# WM1302_v1_1_868_SPI.net
KiCad netlist of a schematic drawn in EAGLE
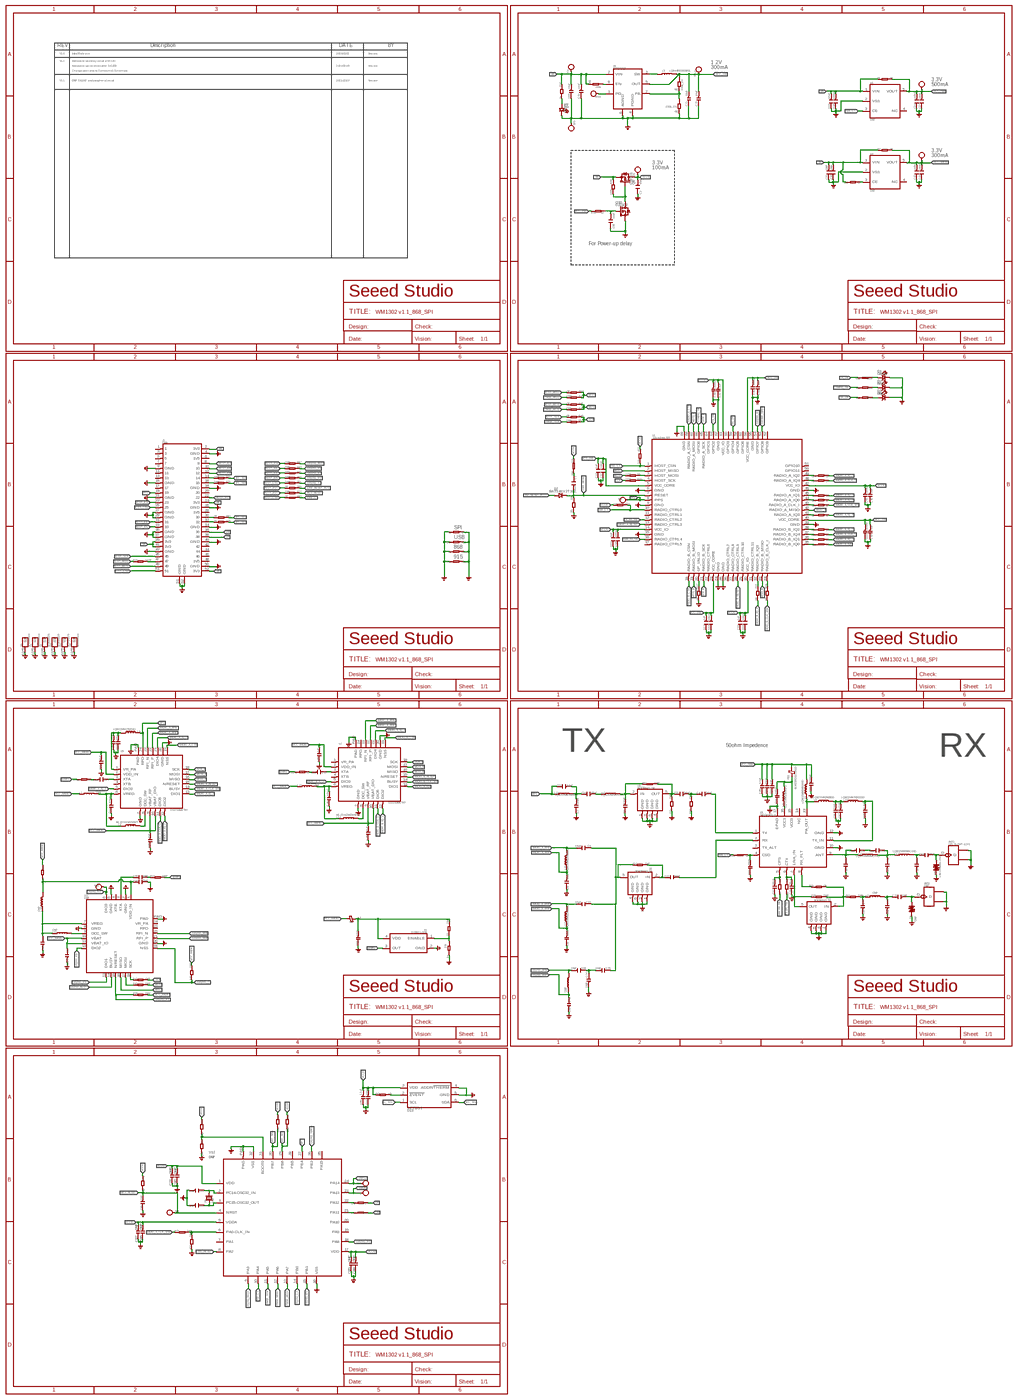
[diagram p0: schematic, sheet 1, overview]
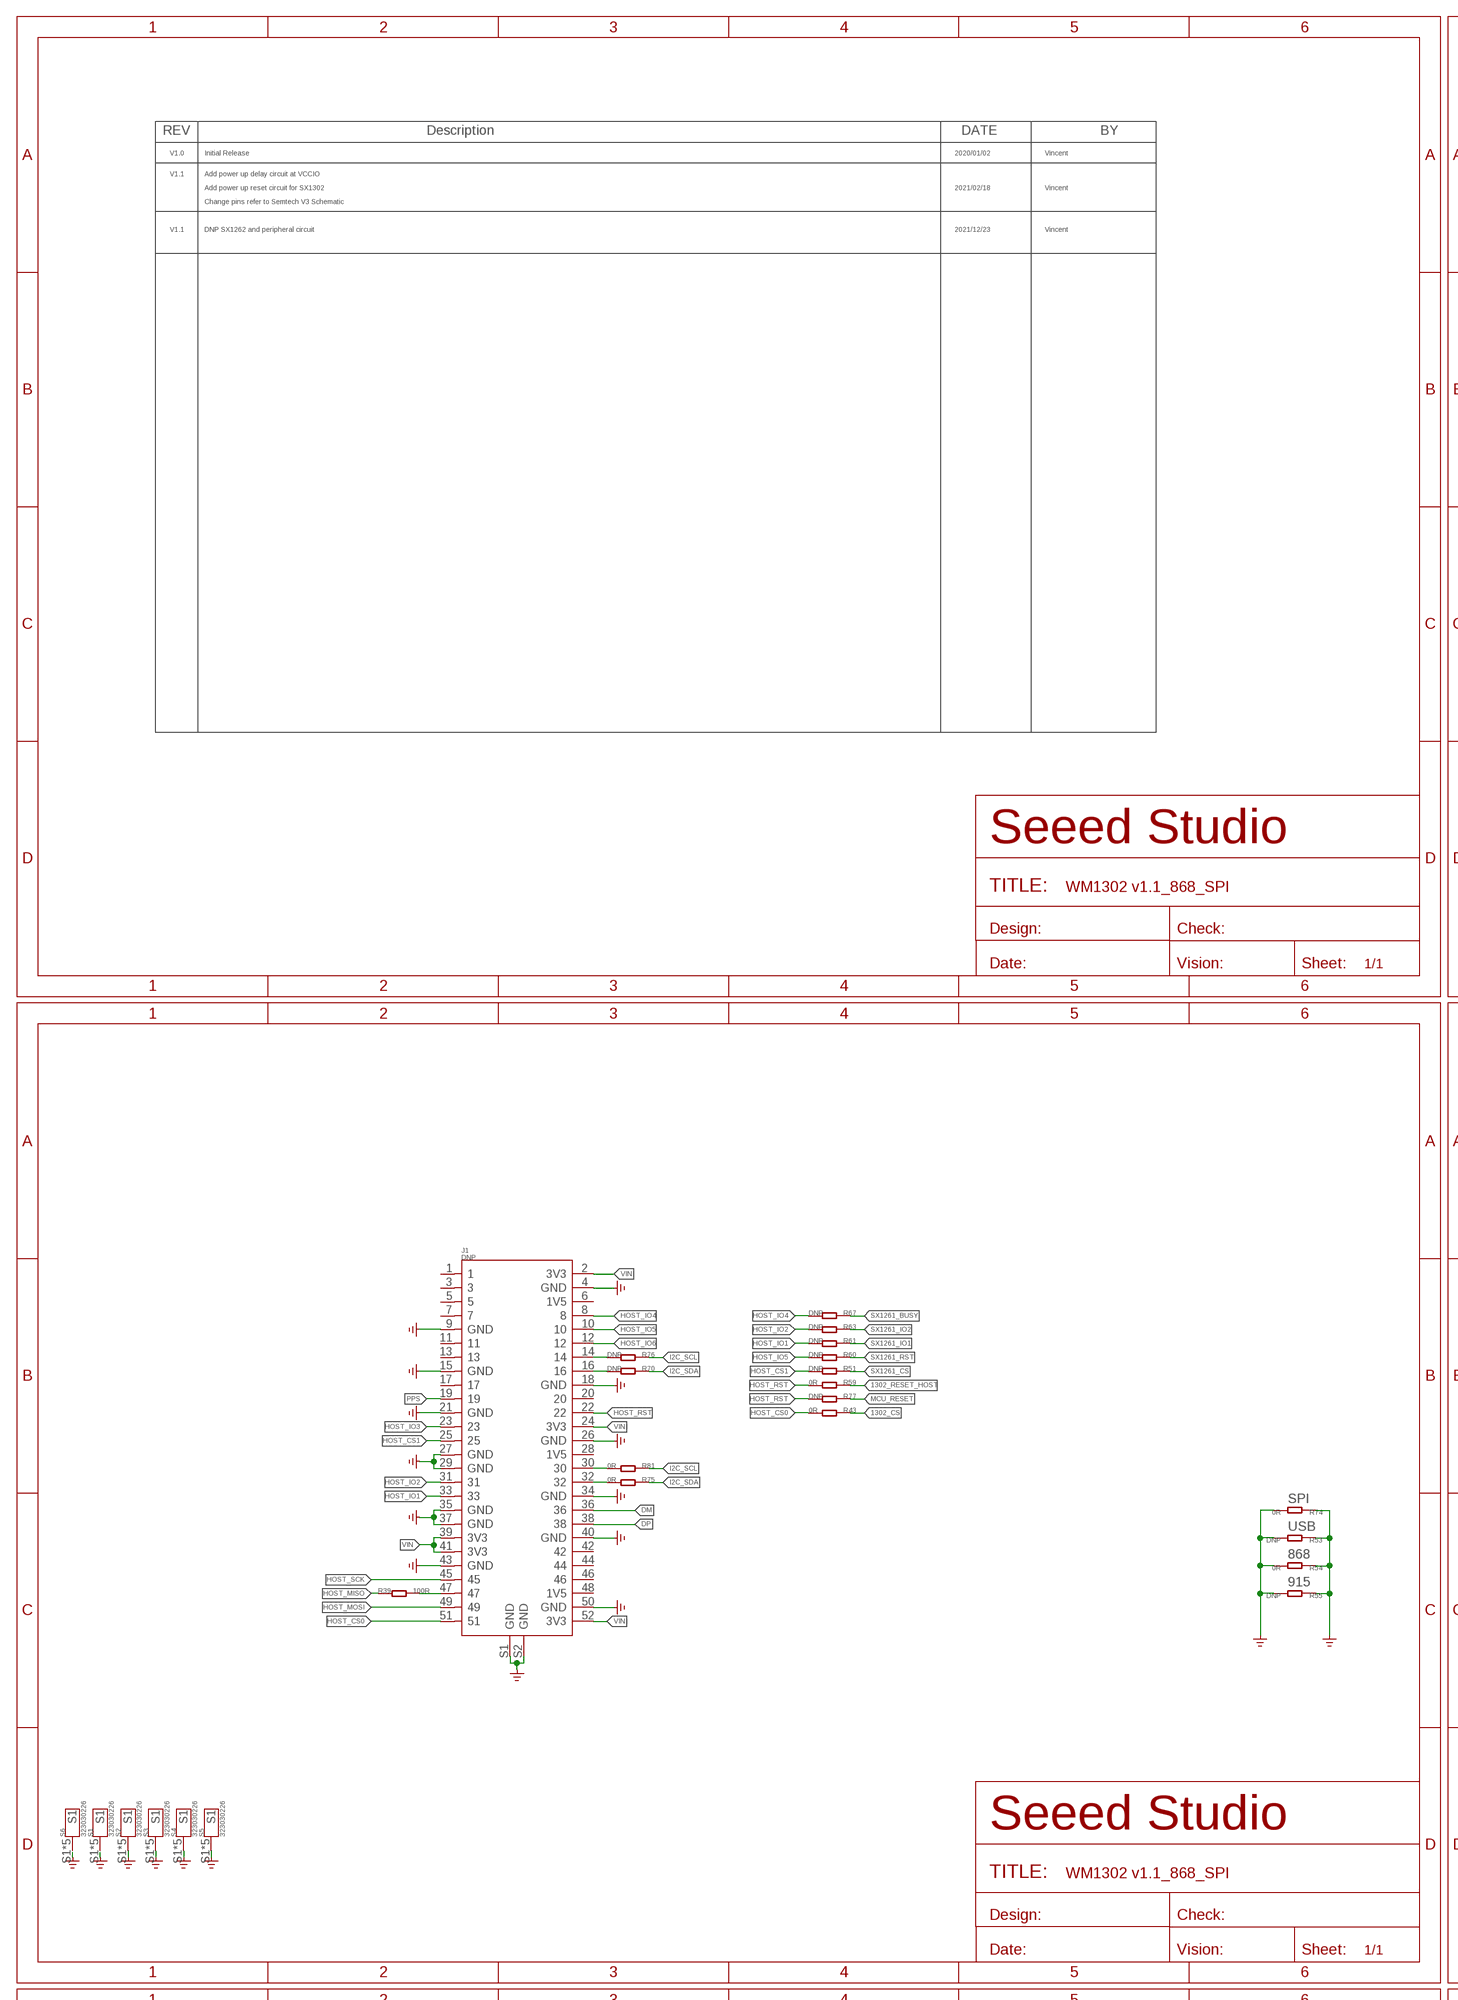
[diagram p1: schematic, sheet 1, part 1 of 4]
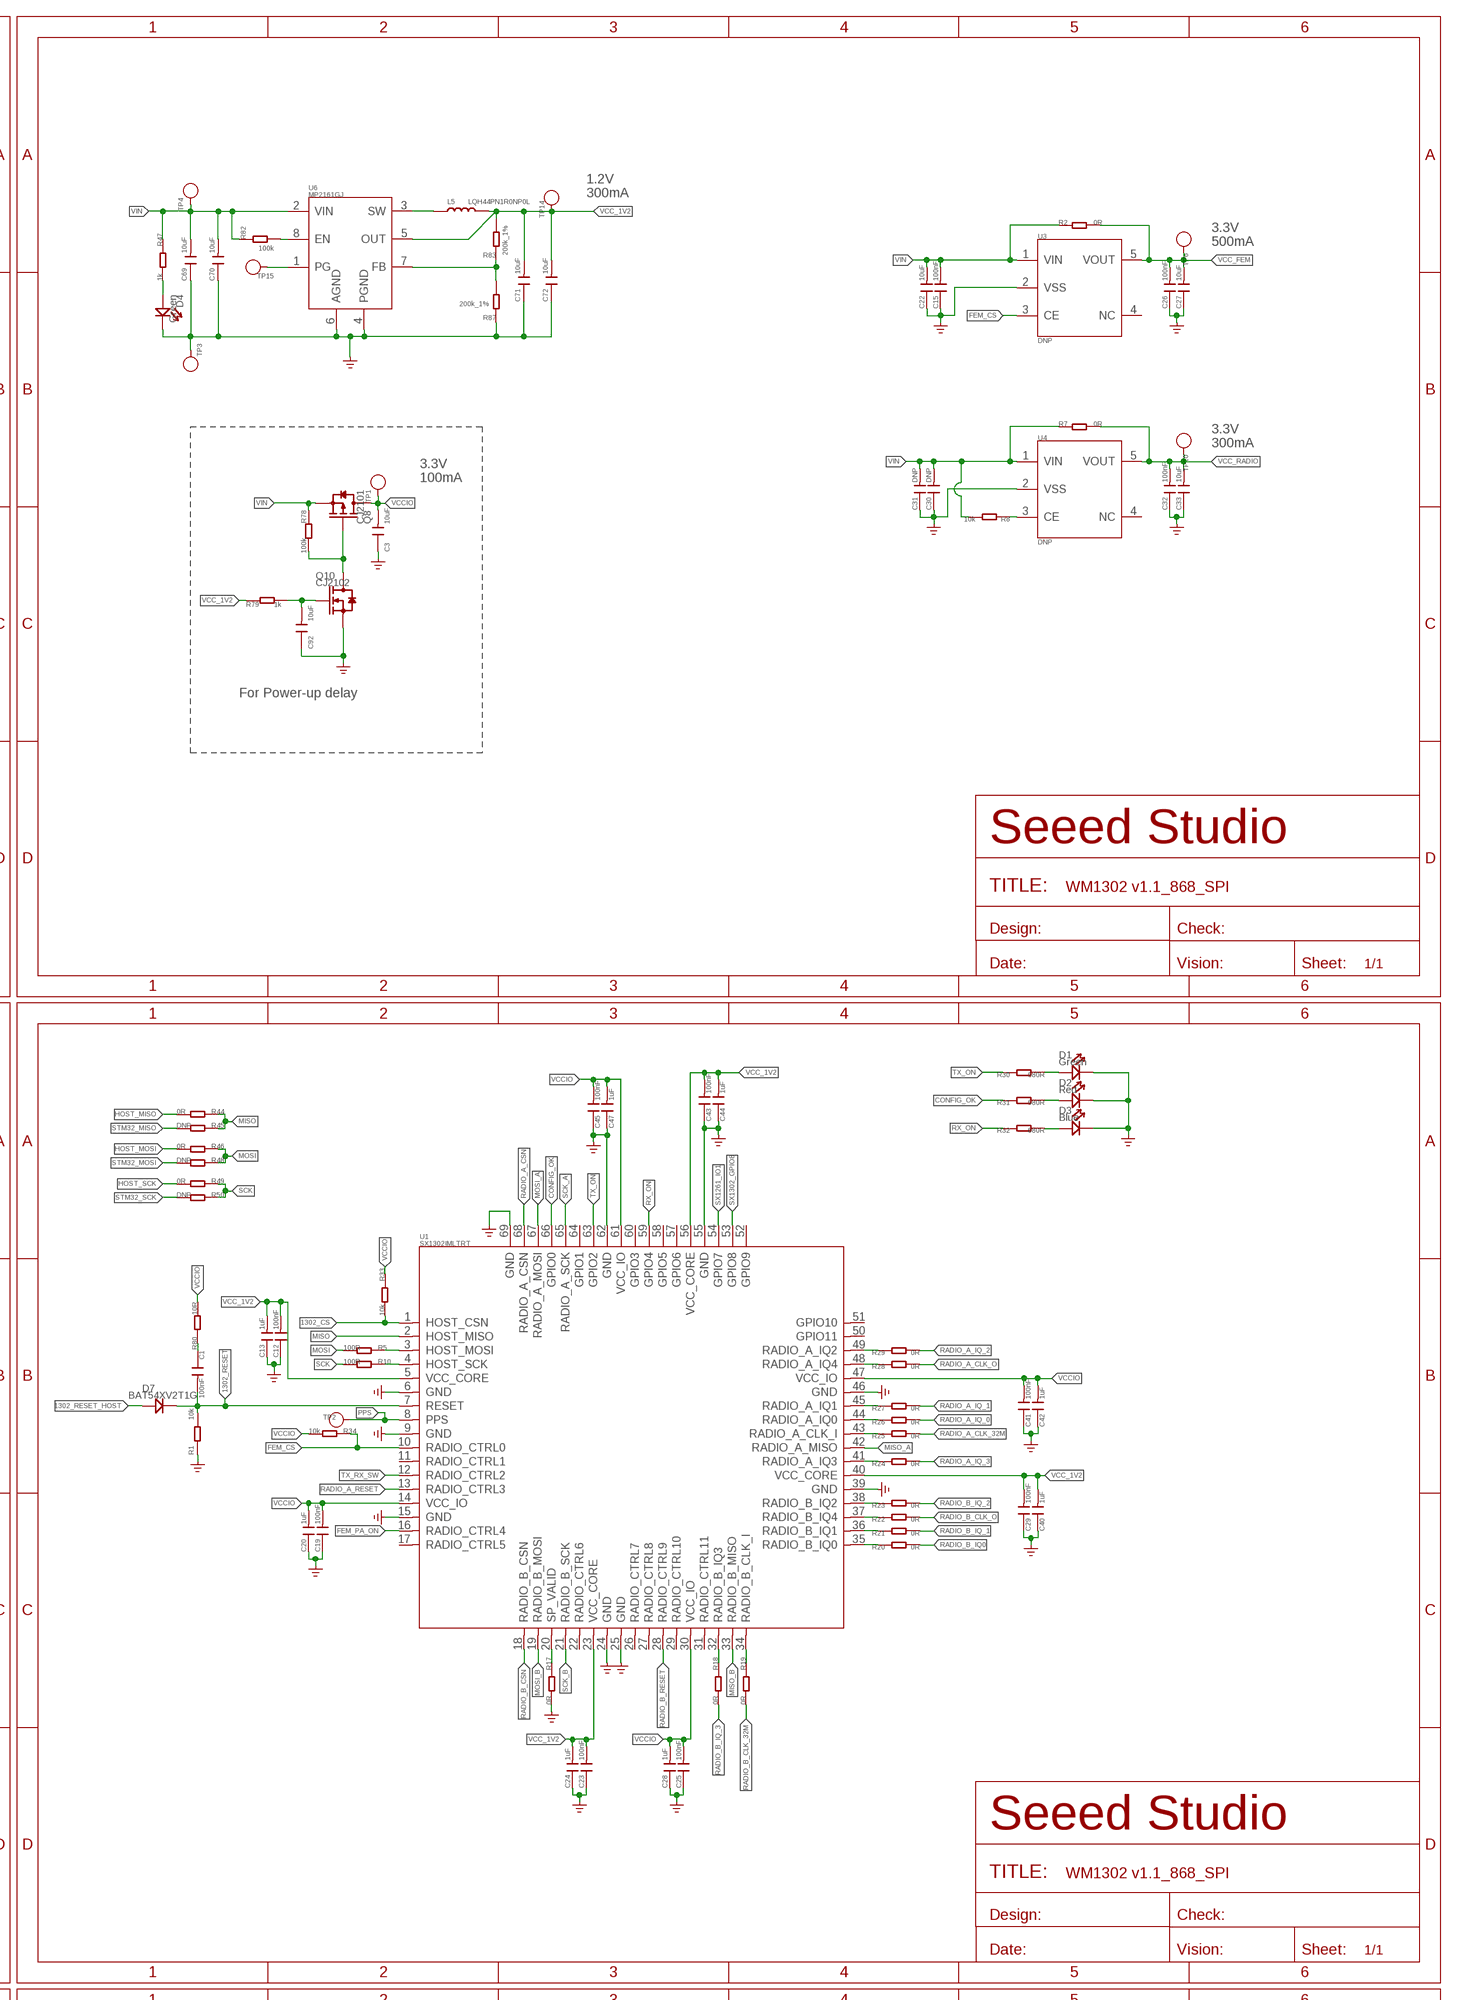
[diagram p2: schematic, sheet 1, part 2 of 4]
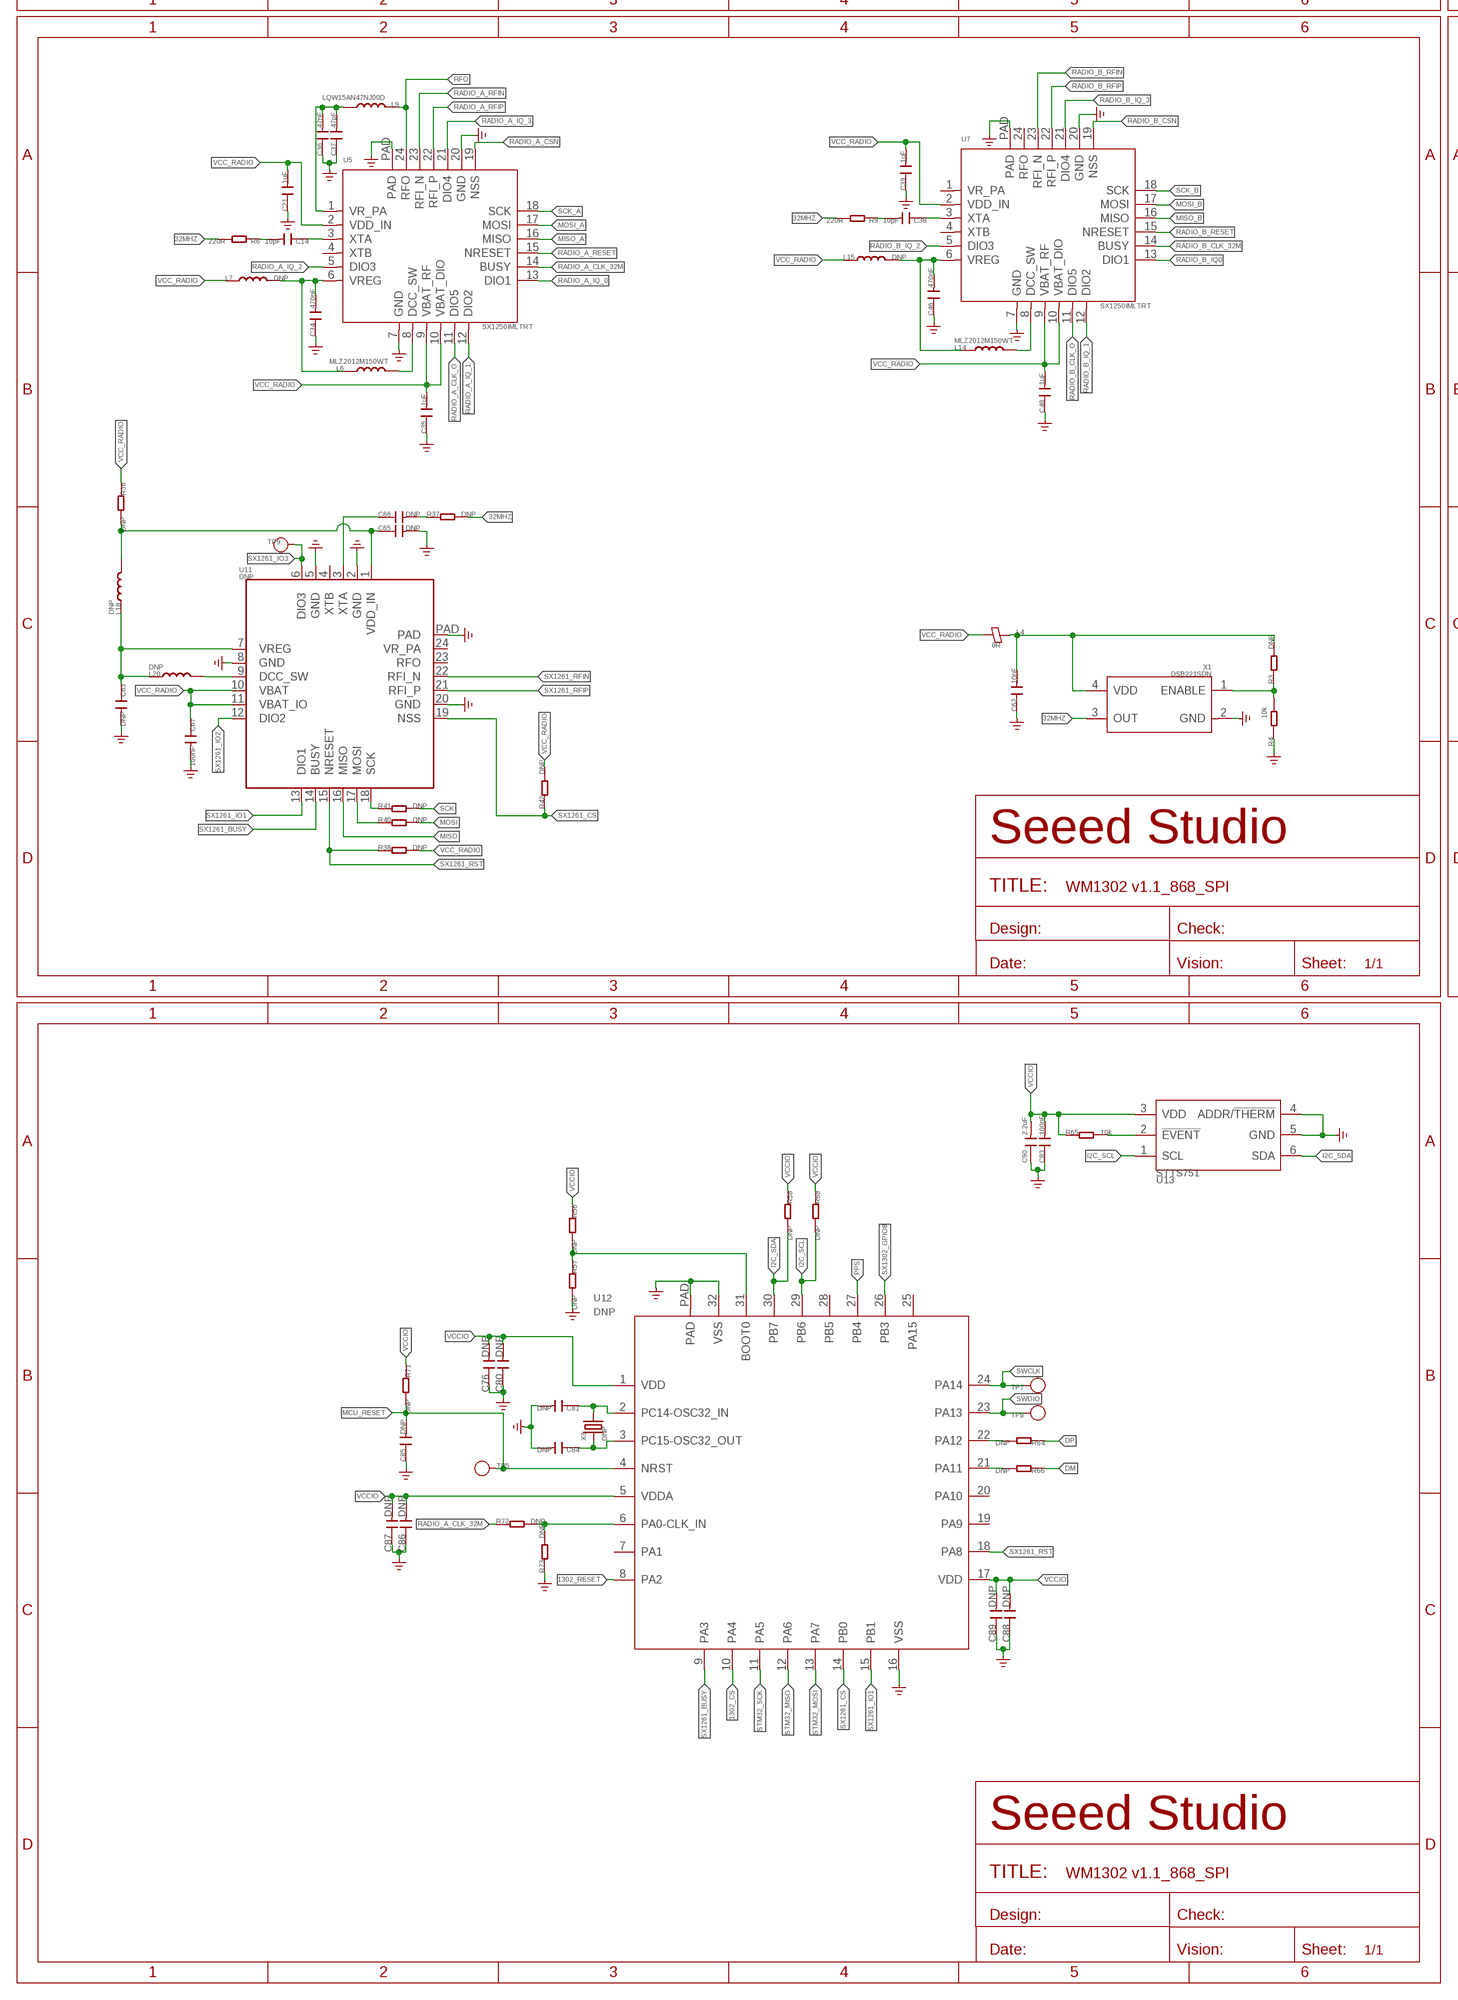
[diagram p3: schematic, sheet 1, part 3 of 4]
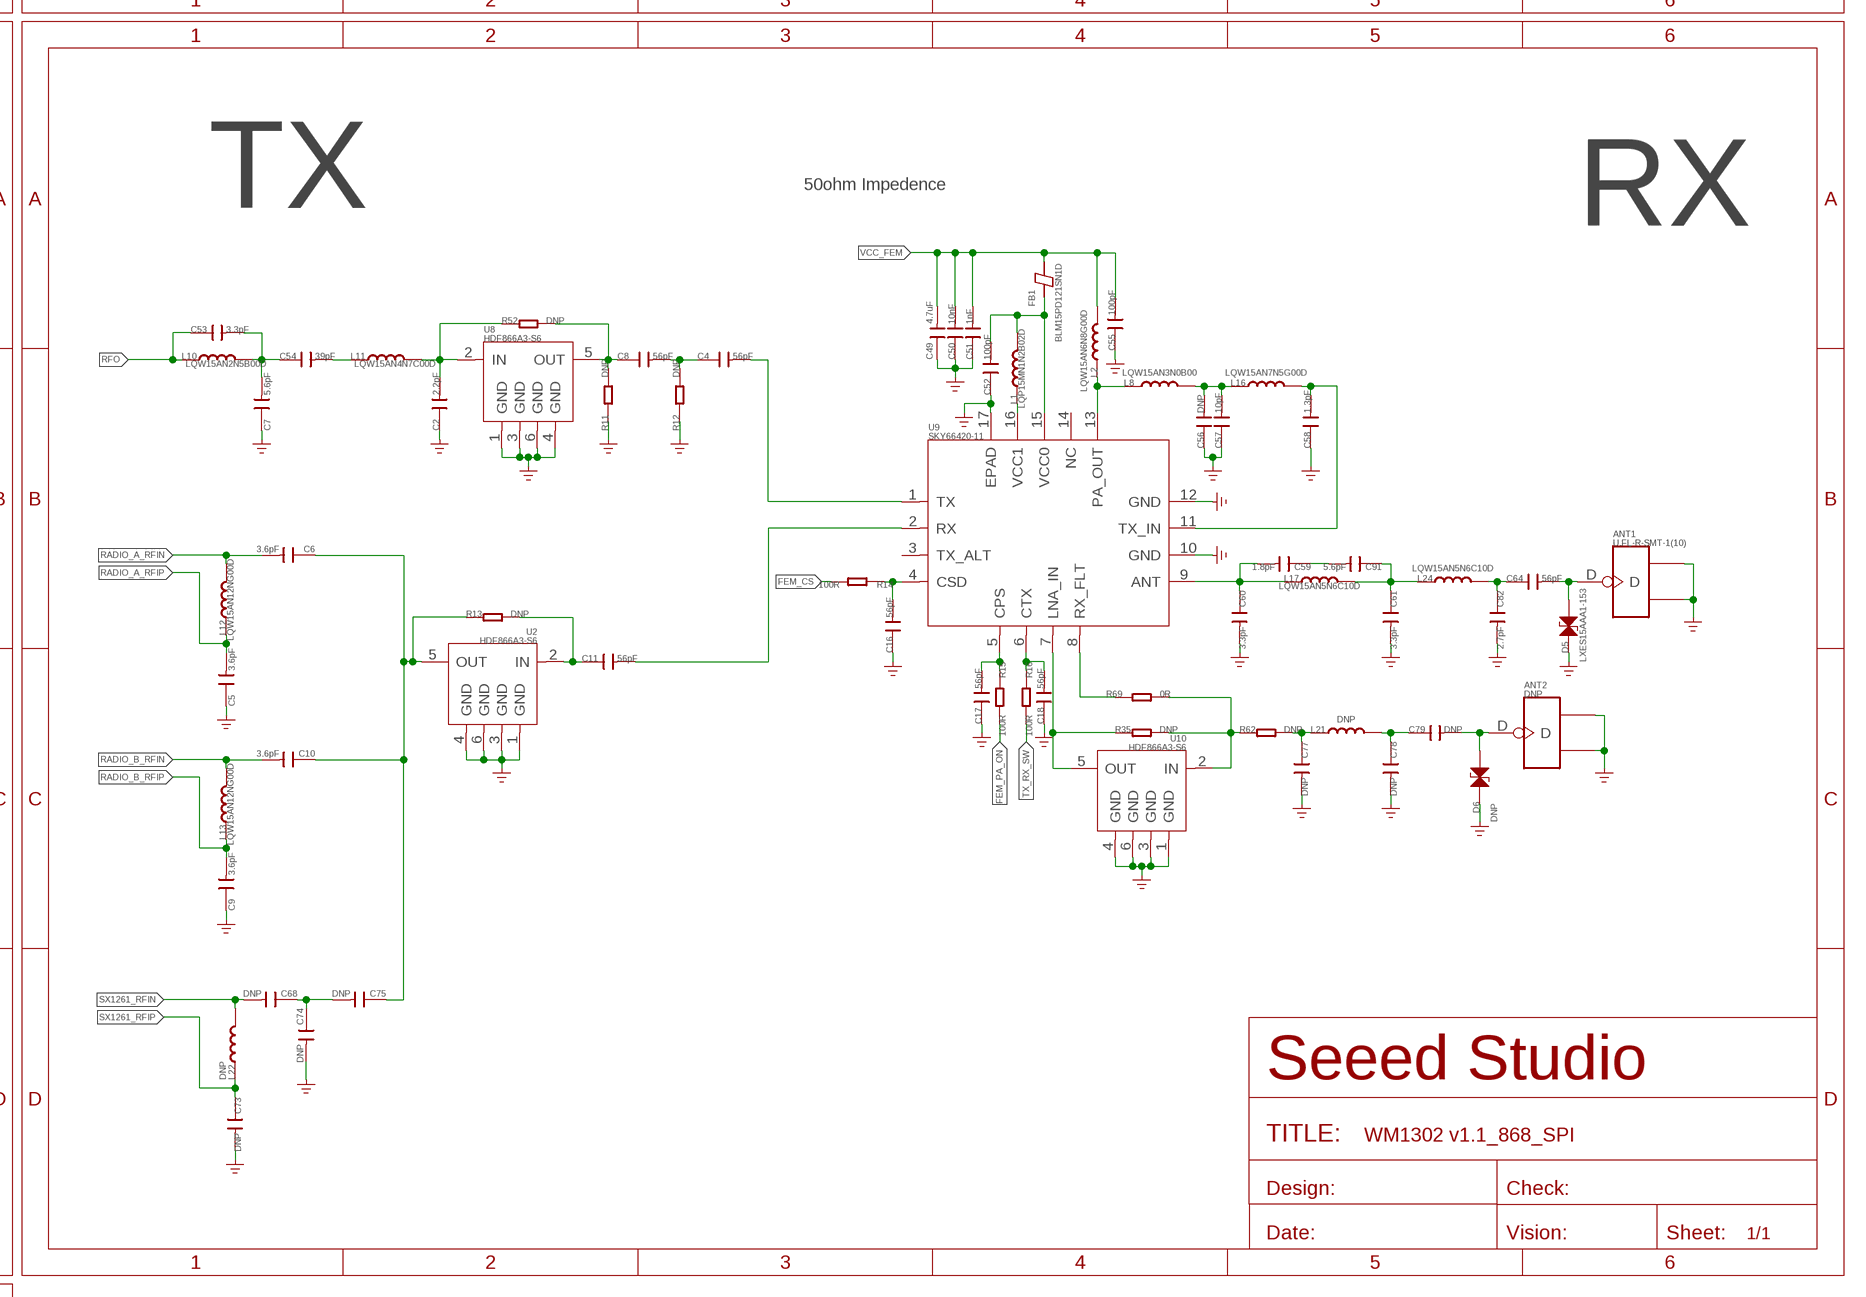
[diagram p4: schematic, sheet 1, part 4 of 4]

(export (version "E")
  (design (tool "Eeschema 10.0.6"))
  (components
    (comp (ref "ANT1")
      (value "U.FL-R-SMT-1(10)")
      (footprint "eagle-import:U-FL3P-SMD-2.6X2.6X1.0MM")
      (fields (field (name "SPICEPREFIX") "J"))
      (libsource (lib "eagle-import") (part "ANTENNA-U-FL-320110048"))
    )
    (comp (ref "ANT2")
      (value "DNP")
      (footprint "eagle-import:U-FL3P-SMD-2.6X2.6X1.0MM")
      (fields (field (name "SPICEPREFIX") "J"))
      (libsource (lib "eagle-import") (part "ANTENNA-U-FL-320110048"))
    )
    (comp (ref "C1")
      (value "100nF")
      (footprint "eagle-import:C0402")
      (libsource (lib "eagle-import") (part "C-0402"))
    )
    (comp (ref "C2")
      (value "2.2pF")
      (footprint "eagle-import:C0402")
      (libsource (lib "eagle-import") (part "C-0402"))
    )
    (comp (ref "C3")
      (value "10uF")
      (footprint "eagle-import:C0603")
      (libsource (lib "eagle-import") (part "C-0603"))
    )
    (comp (ref "C4")
      (value "56pF")
      (footprint "eagle-import:C0402")
      (libsource (lib "eagle-import") (part "C-0402"))
    )
    (comp (ref "C5")
      (value "3.6pF")
      (footprint "eagle-import:C0402")
      (libsource (lib "eagle-import") (part "C-0402"))
    )
    (comp (ref "C6")
      (value "3.6pF")
      (footprint "eagle-import:C0402")
      (libsource (lib "eagle-import") (part "C-0402"))
    )
    (comp (ref "C7")
      (value "5.6pF")
      (footprint "eagle-import:C0402")
      (libsource (lib "eagle-import") (part "C-0402"))
    )
    (comp (ref "C8")
      (value "56pF")
      (footprint "eagle-import:C0402")
      (libsource (lib "eagle-import") (part "C-0402"))
    )
    (comp (ref "C9")
      (value "3.6pF")
      (footprint "eagle-import:C0402")
      (libsource (lib "eagle-import") (part "C-0402"))
    )
    (comp (ref "C10")
      (value "3.6pF")
      (footprint "eagle-import:C0402")
      (libsource (lib "eagle-import") (part "C-0402"))
    )
    (comp (ref "C11")
      (value "56pF")
      (footprint "eagle-import:C0402")
      (libsource (lib "eagle-import") (part "C-0402"))
    )
    (comp (ref "C12")
      (value "100nF")
      (footprint "eagle-import:C0402")
      (libsource (lib "eagle-import") (part "C-0402"))
    )
    (comp (ref "C13")
      (value "1uF")
      (footprint "eagle-import:C0402")
      (libsource (lib "eagle-import") (part "C-0402"))
    )
    (comp (ref "C14")
      (value "10pF")
      (footprint "eagle-import:C0402")
      (libsource (lib "eagle-import") (part "C-0402"))
    )
    (comp (ref "C15")
      (value "100nF")
      (footprint "eagle-import:C0402")
      (libsource (lib "eagle-import") (part "C-0402"))
    )
    (comp (ref "C16")
      (value "56pF")
      (footprint "eagle-import:C0402")
      (libsource (lib "eagle-import") (part "C-0402"))
    )
    (comp (ref "C17")
      (value "56pF")
      (footprint "eagle-import:C0402")
      (libsource (lib "eagle-import") (part "C-0402"))
    )
    (comp (ref "C18")
      (value "56pF")
      (footprint "eagle-import:C0402")
      (libsource (lib "eagle-import") (part "C-0402"))
    )
    (comp (ref "C19")
      (value "100nF")
      (footprint "eagle-import:C0402")
      (libsource (lib "eagle-import") (part "C-0402"))
    )
    (comp (ref "C20")
      (value "1uF")
      (footprint "eagle-import:C0402")
      (libsource (lib "eagle-import") (part "C-0402"))
    )
    (comp (ref "C21")
      (value "1uF")
      (footprint "eagle-import:C0402")
      (libsource (lib "eagle-import") (part "C-0402"))
    )
    (comp (ref "C22")
      (value "10uF")
      (footprint "eagle-import:C0603@1")
      (libsource (lib "eagle-import") (part "CAP-0603"))
    )
    (comp (ref "C23")
      (value "100nF")
      (footprint "eagle-import:C0402")
      (libsource (lib "eagle-import") (part "C-0402"))
    )
    (comp (ref "C24")
      (value "1uF")
      (footprint "eagle-import:C0402")
      (libsource (lib "eagle-import") (part "C-0402"))
    )
    (comp (ref "C25")
      (value "100nF")
      (footprint "eagle-import:C0402")
      (libsource (lib "eagle-import") (part "C-0402"))
    )
    (comp (ref "C26")
      (value "100nF")
      (footprint "eagle-import:C0402")
      (libsource (lib "eagle-import") (part "C-0402"))
    )
    (comp (ref "C27")
      (value "10uF")
      (footprint "eagle-import:C0603@1")
      (libsource (lib "eagle-import") (part "CAP-0603"))
    )
    (comp (ref "C28")
      (value "1uF")
      (footprint "eagle-import:C0402")
      (libsource (lib "eagle-import") (part "C-0402"))
    )
    (comp (ref "C29")
      (value "100nF")
      (footprint "eagle-import:C0402")
      (libsource (lib "eagle-import") (part "C-0402"))
    )
    (comp (ref "C30")
      (value "DNP")
      (footprint "eagle-import:C0402")
      (libsource (lib "eagle-import") (part "C-0402"))
    )
    (comp (ref "C31")
      (value "DNP")
      (footprint "eagle-import:C0603@1")
      (libsource (lib "eagle-import") (part "CAP-0603"))
    )
    (comp (ref "C32")
      (value "100nF")
      (footprint "eagle-import:C0402")
      (libsource (lib "eagle-import") (part "C-0402"))
    )
    (comp (ref "C33")
      (value "10uF")
      (footprint "eagle-import:C0603@1")
      (libsource (lib "eagle-import") (part "CAP-0603"))
    )
    (comp (ref "C34")
      (value "470nF")
      (footprint "eagle-import:C0402")
      (libsource (lib "eagle-import") (part "C-0402"))
    )
    (comp (ref "C35")
      (value "1uF")
      (footprint "eagle-import:C0402")
      (libsource (lib "eagle-import") (part "C-0402"))
    )
    (comp (ref "C36")
      (value "47nF")
      (footprint "eagle-import:C0402")
      (libsource (lib "eagle-import") (part "C-0402"))
    )
    (comp (ref "C37")
      (value "47pF")
      (footprint "eagle-import:C0402")
      (libsource (lib "eagle-import") (part "C-0402"))
    )
    (comp (ref "C38")
      (value "10pF")
      (footprint "eagle-import:C0402")
      (libsource (lib "eagle-import") (part "C-0402"))
    )
    (comp (ref "C39")
      (value "1uF")
      (footprint "eagle-import:C0402")
      (libsource (lib "eagle-import") (part "C-0402"))
    )
    (comp (ref "C40")
      (value "1uF")
      (footprint "eagle-import:C0402")
      (libsource (lib "eagle-import") (part "C-0402"))
    )
    (comp (ref "C41")
      (value "100nF")
      (footprint "eagle-import:C0402")
      (libsource (lib "eagle-import") (part "C-0402"))
    )
    (comp (ref "C42")
      (value "1uF")
      (footprint "eagle-import:C0402")
      (libsource (lib "eagle-import") (part "C-0402"))
    )
    (comp (ref "C43")
      (value "100nF")
      (footprint "eagle-import:C0402")
      (libsource (lib "eagle-import") (part "C-0402"))
    )
    (comp (ref "C44")
      (value "1uF")
      (footprint "eagle-import:C0402")
      (libsource (lib "eagle-import") (part "C-0402"))
    )
    (comp (ref "C45")
      (value "100nF")
      (footprint "eagle-import:C0402")
      (libsource (lib "eagle-import") (part "C-0402"))
    )
    (comp (ref "C46")
      (value "470nF")
      (footprint "eagle-import:C0402")
      (libsource (lib "eagle-import") (part "C-0402"))
    )
    (comp (ref "C47")
      (value "1uF")
      (footprint "eagle-import:C0402")
      (libsource (lib "eagle-import") (part "C-0402"))
    )
    (comp (ref "C48")
      (value "1uF")
      (footprint "eagle-import:C0402")
      (libsource (lib "eagle-import") (part "C-0402"))
    )
    (comp (ref "C49")
      (value "4.7uF")
      (footprint "eagle-import:C0603")
      (libsource (lib "eagle-import") (part "C-0603"))
    )
    (comp (ref "C50")
      (value "10nF")
      (footprint "eagle-import:C0402")
      (libsource (lib "eagle-import") (part "C-0402"))
    )
    (comp (ref "C51")
      (value "1nF")
      (footprint "eagle-import:C0402")
      (libsource (lib "eagle-import") (part "C-0402"))
    )
    (comp (ref "C52")
      (value "100pF")
      (footprint "eagle-import:C0402")
      (libsource (lib "eagle-import") (part "C-0402"))
    )
    (comp (ref "C53")
      (value "3.3pF")
      (footprint "eagle-import:C0402")
      (libsource (lib "eagle-import") (part "C-0402"))
    )
    (comp (ref "C54")
      (value "39pF")
      (footprint "eagle-import:C0402")
      (libsource (lib "eagle-import") (part "C-0402"))
    )
    (comp (ref "C55")
      (value "100pF")
      (footprint "eagle-import:C0402")
      (fields (field (name "SPICEPREFIX") "C"))
      (libsource (lib "eagle-import") (part "C-0402"))
    )
    (comp (ref "C56")
      (value "DNP")
      (footprint "eagle-import:C0402")
      (libsource (lib "eagle-import") (part "C-0402"))
    )
    (comp (ref "C57")
      (value "10pF")
      (footprint "eagle-import:C0402")
      (libsource (lib "eagle-import") (part "C-0402"))
    )
    (comp (ref "C58")
      (value "1.3pF")
      (footprint "eagle-import:C0402")
      (libsource (lib "eagle-import") (part "C-0402"))
    )
    (comp (ref "C59")
      (value "1.8pF")
      (footprint "eagle-import:C0402")
      (libsource (lib "eagle-import") (part "C-0402"))
    )
    (comp (ref "C60")
      (value "3.3pF")
      (footprint "eagle-import:C0402")
      (libsource (lib "eagle-import") (part "C-0402"))
    )
    (comp (ref "C61")
      (value "3.3pF")
      (footprint "eagle-import:C0402")
      (libsource (lib "eagle-import") (part "C-0402"))
    )
    (comp (ref "C62")
      (value "10nF")
      (footprint "eagle-import:C0402")
      (libsource (lib "eagle-import") (part "C-0402"))
    )
    (comp (ref "C63")
      (value "DNP")
      (footprint "eagle-import:C0402")
      (libsource (lib "eagle-import") (part "C-0402"))
    )
    (comp (ref "C64")
      (value "56pF")
      (footprint "eagle-import:C0402")
      (libsource (lib "eagle-import") (part "C-0402"))
    )
    (comp (ref "C65")
      (value "DNP")
      (footprint "eagle-import:C0402")
      (libsource (lib "eagle-import") (part "C-0402"))
    )
    (comp (ref "C66")
      (value "DNP")
      (footprint "eagle-import:C0402")
      (libsource (lib "eagle-import") (part "C-0402"))
    )
    (comp (ref "C67")
      (value "100nF")
      (footprint "eagle-import:C0402")
      (libsource (lib "eagle-import") (part "C-0402"))
    )
    (comp (ref "C68")
      (value "DNP")
      (footprint "eagle-import:C0402")
      (libsource (lib "eagle-import") (part "C-0402"))
    )
    (comp (ref "C69")
      (value "10uF")
      (footprint "eagle-import:C0805")
      (libsource (lib "eagle-import") (part "CAP-0805"))
    )
    (comp (ref "C70")
      (value "10uF")
      (footprint "eagle-import:C0805")
      (libsource (lib "eagle-import") (part "CAP-0805"))
    )
    (comp (ref "C71")
      (value "10uF")
      (footprint "eagle-import:C0805")
      (libsource (lib "eagle-import") (part "CAP-0805"))
    )
    (comp (ref "C72")
      (value "10uF")
      (footprint "eagle-import:C0805")
      (libsource (lib "eagle-import") (part "CAP-0805"))
    )
    (comp (ref "C73")
      (value "DNP")
      (footprint "eagle-import:C0402")
      (libsource (lib "eagle-import") (part "C-0402"))
    )
    (comp (ref "C74")
      (value "DNP")
      (footprint "eagle-import:C0402")
      (libsource (lib "eagle-import") (part "C-0402"))
    )
    (comp (ref "C75")
      (value "DNP")
      (footprint "eagle-import:C0402")
      (libsource (lib "eagle-import") (part "C-0402"))
    )
    (comp (ref "C76")
      (value "DNP")
      (footprint "eagle-import:C0402")
      (libsource (lib "eagle-import") (part "C-0402"))
    )
    (comp (ref "C77")
      (value "DNP")
      (footprint "eagle-import:C0402")
      (libsource (lib "eagle-import") (part "C-0402"))
    )
    (comp (ref "C78")
      (value "DNP")
      (footprint "eagle-import:C0402")
      (libsource (lib "eagle-import") (part "C-0402"))
    )
    (comp (ref "C79")
      (value "DNP")
      (footprint "eagle-import:C0402")
      (libsource (lib "eagle-import") (part "C-0402"))
    )
    (comp (ref "C80")
      (value "DNP")
      (footprint "eagle-import:C0402")
      (libsource (lib "eagle-import") (part "C-0402"))
    )
    (comp (ref "C81")
      (value "DNP")
      (footprint "eagle-import:C0402")
      (libsource (lib "eagle-import") (part "C-0402"))
    )
    (comp (ref "C82")
      (value "2.7pF")
      (footprint "eagle-import:C0402")
      (libsource (lib "eagle-import") (part "C-0402"))
    )
    (comp (ref "C83")
      (value "100nF")
      (footprint "eagle-import:C0402")
      (libsource (lib "eagle-import") (part "C-0402"))
    )
    (comp (ref "C84")
      (value "DNP")
      (footprint "eagle-import:C0402")
      (libsource (lib "eagle-import") (part "C-0402"))
    )
    (comp (ref "C85")
      (value "DNP")
      (footprint "eagle-import:C0402")
      (libsource (lib "eagle-import") (part "C-0402"))
    )
    (comp (ref "C86")
      (value "DNP")
      (footprint "eagle-import:C0402")
      (libsource (lib "eagle-import") (part "C-0402"))
    )
    (comp (ref "C87")
      (value "DNP")
      (footprint "eagle-import:C0402")
      (libsource (lib "eagle-import") (part "C-0402"))
    )
    (comp (ref "C88")
      (value "DNP")
      (footprint "eagle-import:C0402")
      (libsource (lib "eagle-import") (part "C-0402"))
    )
    (comp (ref "C89")
      (value "DNP")
      (footprint "eagle-import:C0402")
      (libsource (lib "eagle-import") (part "C-0402"))
    )
    (comp (ref "C90")
      (value "2.2uF")
      (footprint "eagle-import:C0603")
      (libsource (lib "eagle-import") (part "C-0603"))
    )
    (comp (ref "C91")
      (value "5.6pF")
      (footprint "eagle-import:C0402")
      (libsource (lib "eagle-import") (part "C-0402"))
    )
    (comp (ref "C92")
      (value "10uF")
      (footprint "eagle-import:C0603")
      (libsource (lib "eagle-import") (part "C-0603"))
    )
    (comp (ref "D1")
      (value "Green")
      (footprint "eagle-import:LED-0402")
      (libsource (lib "eagle-import") (part "LED-0402"))
    )
    (comp (ref "D2")
      (value "Red")
      (footprint "eagle-import:LED-0402")
      (libsource (lib "eagle-import") (part "LED-0402"))
    )
    (comp (ref "D3")
      (value "Blue")
      (footprint "eagle-import:LED-0402")
      (libsource (lib "eagle-import") (part "LED-0402"))
    )
    (comp (ref "D4")
      (value "Green")
      (footprint "eagle-import:LED-0402")
      (libsource (lib "eagle-import") (part "LED-0402"))
    )
    (comp (ref "D5")
      (value "LXES15AAA1-153")
      (footprint "eagle-import:ESD-0402")
      (libsource (lib "eagle-import") (part "D-ESD-2P-DOUBLE-0402"))
    )
    (comp (ref "D6")
      (value "DNP")
      (footprint "eagle-import:ESD-0402")
      (libsource (lib "eagle-import") (part "D-ESD-2P-DOUBLE-0402"))
    )
    (comp (ref "D7")
      (value "BAT54XV2T1G")
      (footprint "eagle-import:SOD-523")
      (libsource (lib "eagle-import") (part "DIODE'0603'"))
    )
    (comp (ref "FB1")
      (value "BLM15PD121SN1D")
      (footprint "eagle-import:F0402")
      (libsource (lib "eagle-import") (part "FERRITE-BEAD-0402"))
    )
    (comp (ref "J1")
      (value "DNP")
      (footprint "eagle-import:PCIE52P-0.8-50.95X30MM")
      (libsource (lib "eagle-import") (part "MOUDLE-FULL-MINI-PCIE"))
    )
    (comp (ref "L1")
      (value "LQP15MN1N2B02D")
      (footprint "eagle-import:L0402")
      (libsource (lib "eagle-import") (part "L-0402"))
    )
    (comp (ref "L2")
      (value "LQW15AN6N8G00D")
      (footprint "eagle-import:L0402")
      (libsource (lib "eagle-import") (part "L-0402"))
    )
    (comp (ref "L4")
      (value "0R")
      (footprint "eagle-import:F0603")
      (libsource (lib "eagle-import") (part "FERRITE-BEAD-0603"))
    )
    (comp (ref "L5")
      (value "LQH44PN1R0NP0L")
      (footprint "eagle-import:L4.4X3.0MM")
      (libsource (lib "eagle-import") (part "INDUCTOR-4430"))
    )
    (comp (ref "L6")
      (value "MLZ2012M150WT")
      (footprint "eagle-import:L0805")
      (libsource (lib "eagle-import") (part "L-0805"))
    )
    (comp (ref "L7")
      (value "DNP")
      (footprint "eagle-import:L0402")
      (libsource (lib "eagle-import") (part "L-0402"))
    )
    (comp (ref "L8")
      (value "LQW15AN3N0B00")
      (footprint "eagle-import:L0402")
      (libsource (lib "eagle-import") (part "L-0402"))
    )
    (comp (ref "L9")
      (value "LQW15AN47NJ00D")
      (footprint "eagle-import:L0402")
      (libsource (lib "eagle-import") (part "L-0402"))
    )
    (comp (ref "L10")
      (value "LQW15AN2N5B00D")
      (footprint "eagle-import:L0402")
      (libsource (lib "eagle-import") (part "L-0402"))
    )
    (comp (ref "L11")
      (value "LQW15AN4N7C00D")
      (footprint "eagle-import:L0402")
      (libsource (lib "eagle-import") (part "L-0402"))
    )
    (comp (ref "L12")
      (value "LQW15AN12NG00D")
      (footprint "eagle-import:L0402")
      (libsource (lib "eagle-import") (part "L-0402"))
    )
    (comp (ref "L13")
      (value "LQW15AN12NG00D")
      (footprint "eagle-import:L0402")
      (libsource (lib "eagle-import") (part "L-0402"))
    )
    (comp (ref "L14")
      (value "MLZ2012M150WT")
      (footprint "eagle-import:L0805")
      (libsource (lib "eagle-import") (part "L-0805"))
    )
    (comp (ref "L15")
      (value "DNP")
      (footprint "eagle-import:L0402")
      (libsource (lib "eagle-import") (part "L-0402"))
    )
    (comp (ref "L16")
      (value "LQW15AN7N5G00D")
      (footprint "eagle-import:L0402")
      (libsource (lib "eagle-import") (part "L-0402"))
    )
    (comp (ref "L17")
      (value "LQW15AN5N6C10D")
      (footprint "eagle-import:L0402")
      (libsource (lib "eagle-import") (part "L-0402"))
    )
    (comp (ref "L18")
      (value "DNP")
      (footprint "eagle-import:L0402")
      (libsource (lib "eagle-import") (part "L-0402"))
    )
    (comp (ref "L20")
      (value "DNP")
      (footprint "eagle-import:L0805")
      (libsource (lib "eagle-import") (part "L-0805"))
    )
    (comp (ref "L21")
      (value "DNP")
      (footprint "eagle-import:L0402")
      (libsource (lib "eagle-import") (part "L-0402"))
    )
    (comp (ref "L22")
      (value "DNP")
      (footprint "eagle-import:L0402")
      (libsource (lib "eagle-import") (part "L-0402"))
    )
    (comp (ref "L24")
      (value "LQW15AN5N6C10D")
      (footprint "eagle-import:L0402")
      (libsource (lib "eagle-import") (part "L-0402"))
    )
    (comp (ref "Q8")
      (value "CJ2101")
      (footprint "eagle-import:SOT-323")
      (libsource (lib "eagle-import") (part "MOSFET-P-SOT323"))
    )
    (comp (ref "Q10")
      (value "CJ2102")
      (footprint "eagle-import:SOT-323")
      (libsource (lib "eagle-import") (part "MOSFET-N-SI1304BDL"))
    )
    (comp (ref "R1")
      (value "10k")
      (footprint "eagle-import:R0402")
      (libsource (lib "eagle-import") (part "R-0402"))
    )
    (comp (ref "R2")
      (value "0R")
      (footprint "eagle-import:R0603")
      (libsource (lib "eagle-import") (part "R-0603"))
    )
    (comp (ref "R3")
      (value "DNP")
      (footprint "eagle-import:R0402")
      (libsource (lib "eagle-import") (part "R-0402"))
    )
    (comp (ref "R4")
      (value "10k")
      (footprint "eagle-import:R0402")
      (libsource (lib "eagle-import") (part "R-0402"))
    )
    (comp (ref "R5")
      (value "100R")
      (footprint "eagle-import:R0402")
      (libsource (lib "eagle-import") (part "R-0402"))
    )
    (comp (ref "R6")
      (value "220R")
      (footprint "eagle-import:R0402")
      (libsource (lib "eagle-import") (part "R-0402"))
    )
    (comp (ref "R7")
      (value "0R")
      (footprint "eagle-import:R0603")
      (libsource (lib "eagle-import") (part "R-0603"))
    )
    (comp (ref "R8")
      (value "10k")
      (footprint "eagle-import:R0402")
      (libsource (lib "eagle-import") (part "R-0402"))
    )
    (comp (ref "R9")
      (value "220R")
      (footprint "eagle-import:R0402")
      (libsource (lib "eagle-import") (part "R-0402"))
    )
    (comp (ref "R10")
      (value "100R")
      (footprint "eagle-import:R0402")
      (libsource (lib "eagle-import") (part "R-0402"))
    )
    (comp (ref "R11")
      (value "DNP")
      (footprint "eagle-import:R0402")
      (libsource (lib "eagle-import") (part "R-0402"))
    )
    (comp (ref "R12")
      (value "DNP")
      (footprint "eagle-import:R0402")
      (libsource (lib "eagle-import") (part "R-0402"))
    )
    (comp (ref "R13")
      (value "DNP")
      (footprint "eagle-import:R0603")
      (libsource (lib "eagle-import") (part "RES-0603"))
    )
    (comp (ref "R14")
      (value "100R")
      (footprint "eagle-import:R0402")
      (libsource (lib "eagle-import") (part "R-0402"))
    )
    (comp (ref "R15")
      (value "100R")
      (footprint "eagle-import:R0402")
      (libsource (lib "eagle-import") (part "R-0402"))
    )
    (comp (ref "R16")
      (value "100R")
      (footprint "eagle-import:R0402")
      (libsource (lib "eagle-import") (part "R-0402"))
    )
    (comp (ref "R17")
      (value "0R")
      (footprint "eagle-import:R0402")
      (libsource (lib "eagle-import") (part "R-0402"))
    )
    (comp (ref "R18")
      (value "0R")
      (footprint "eagle-import:R0402")
      (libsource (lib "eagle-import") (part "R-0402"))
    )
    (comp (ref "R19")
      (value "0R")
      (footprint "eagle-import:R0402")
      (libsource (lib "eagle-import") (part "R-0402"))
    )
    (comp (ref "R20")
      (value "0R")
      (footprint "eagle-import:R0402")
      (libsource (lib "eagle-import") (part "R-0402"))
    )
    (comp (ref "R21")
      (value "0R")
      (footprint "eagle-import:R0402")
      (libsource (lib "eagle-import") (part "R-0402"))
    )
    (comp (ref "R22")
      (value "0R")
      (footprint "eagle-import:R0402")
      (libsource (lib "eagle-import") (part "R-0402"))
    )
    (comp (ref "R23")
      (value "0R")
      (footprint "eagle-import:R0402")
      (libsource (lib "eagle-import") (part "R-0402"))
    )
    (comp (ref "R24")
      (value "0R")
      (footprint "eagle-import:R0402")
      (libsource (lib "eagle-import") (part "R-0402"))
    )
    (comp (ref "R25")
      (value "0R")
      (footprint "eagle-import:R0402")
      (libsource (lib "eagle-import") (part "R-0402"))
    )
    (comp (ref "R26")
      (value "0R")
      (footprint "eagle-import:R0402")
      (libsource (lib "eagle-import") (part "R-0402"))
    )
    (comp (ref "R27")
      (value "0R")
      (footprint "eagle-import:R0402")
      (libsource (lib "eagle-import") (part "R-0402"))
    )
    (comp (ref "R28")
      (value "0R")
      (footprint "eagle-import:R0402")
      (libsource (lib "eagle-import") (part "R-0402"))
    )
    (comp (ref "R29")
      (value "0R")
      (footprint "eagle-import:R0402")
      (libsource (lib "eagle-import") (part "R-0402"))
    )
    (comp (ref "R30")
      (value "680R")
      (footprint "eagle-import:R0402")
      (libsource (lib "eagle-import") (part "R-0402"))
    )
    (comp (ref "R31")
      (value "680R")
      (footprint "eagle-import:R0402")
      (libsource (lib "eagle-import") (part "R-0402"))
    )
    (comp (ref "R32")
      (value "680R")
      (footprint "eagle-import:R0402")
      (libsource (lib "eagle-import") (part "R-0402"))
    )
    (comp (ref "R33")
      (value "10k")
      (footprint "eagle-import:R0402")
      (libsource (lib "eagle-import") (part "R-0402"))
    )
    (comp (ref "R34")
      (value "10k")
      (footprint "eagle-import:R0402")
      (libsource (lib "eagle-import") (part "R-0402"))
    )
    (comp (ref "R35")
      (value "DNP")
      (footprint "eagle-import:R0603")
      (libsource (lib "eagle-import") (part "RES-0603"))
    )
    (comp (ref "R36")
      (value "DNP")
      (footprint "eagle-import:R0402")
      (libsource (lib "eagle-import") (part "R-0402"))
    )
    (comp (ref "R37")
      (value "DNP")
      (footprint "eagle-import:R0402")
      (libsource (lib "eagle-import") (part "R-0402"))
    )
    (comp (ref "R38")
      (value "DNP")
      (footprint "eagle-import:R0402")
      (libsource (lib "eagle-import") (part "R-0402"))
    )
    (comp (ref "R39")
      (value "100R")
      (footprint "eagle-import:R0402")
      (libsource (lib "eagle-import") (part "R-0402"))
    )
    (comp (ref "R40")
      (value "DNP")
      (footprint "eagle-import:R0402")
      (libsource (lib "eagle-import") (part "R-0402"))
    )
    (comp (ref "R41")
      (value "DNP")
      (footprint "eagle-import:R0402")
      (libsource (lib "eagle-import") (part "R-0402"))
    )
    (comp (ref "R42")
      (value "DNP")
      (footprint "eagle-import:R0402")
      (libsource (lib "eagle-import") (part "R-0402"))
    )
    (comp (ref "R43")
      (value "0R")
      (footprint "eagle-import:R0402")
      (libsource (lib "eagle-import") (part "R-0402"))
    )
    (comp (ref "R44")
      (value "0R")
      (footprint "eagle-import:R0402")
      (libsource (lib "eagle-import") (part "R-0402"))
    )
    (comp (ref "R45")
      (value "DNP")
      (footprint "eagle-import:R0402")
      (libsource (lib "eagle-import") (part "R-0402"))
    )
    (comp (ref "R46")
      (value "0R")
      (footprint "eagle-import:R0402")
      (libsource (lib "eagle-import") (part "R-0402"))
    )
    (comp (ref "R47")
      (value "1k")
      (footprint "eagle-import:R0402")
      (libsource (lib "eagle-import") (part "R-0402"))
    )
    (comp (ref "R48")
      (value "DNP")
      (footprint "eagle-import:R0402")
      (libsource (lib "eagle-import") (part "R-0402"))
    )
    (comp (ref "R49")
      (value "0R")
      (footprint "eagle-import:R0402")
      (libsource (lib "eagle-import") (part "R-0402"))
    )
    (comp (ref "R50")
      (value "DNP")
      (footprint "eagle-import:R0402")
      (libsource (lib "eagle-import") (part "R-0402"))
    )
    (comp (ref "R51")
      (value "DNP")
      (footprint "eagle-import:R0402")
      (libsource (lib "eagle-import") (part "R-0402"))
    )
    (comp (ref "R52")
      (value "DNP")
      (footprint "eagle-import:R0603")
      (libsource (lib "eagle-import") (part "RES-0603"))
    )
    (comp (ref "R53")
      (value "DNP")
      (footprint "eagle-import:R0402")
      (libsource (lib "eagle-import") (part "R-0402"))
    )
    (comp (ref "R54")
      (value "0R")
      (footprint "eagle-import:R0402")
      (libsource (lib "eagle-import") (part "R-0402"))
    )
    (comp (ref "R55")
      (value "DNP")
      (footprint "eagle-import:R0402")
      (libsource (lib "eagle-import") (part "R-0402"))
    )
    (comp (ref "R56")
      (value "DNP")
      (footprint "eagle-import:R0402")
      (libsource (lib "eagle-import") (part "R-0402"))
    )
    (comp (ref "R57")
      (value "DNP")
      (footprint "eagle-import:R0402")
      (libsource (lib "eagle-import") (part "R-0402"))
    )
    (comp (ref "R58")
      (value "DNP")
      (footprint "eagle-import:R0402")
      (libsource (lib "eagle-import") (part "R-0402"))
    )
    (comp (ref "R59")
      (value "0R")
      (footprint "eagle-import:R0402")
      (libsource (lib "eagle-import") (part "R-0402"))
    )
    (comp (ref "R60")
      (value "DNP")
      (footprint "eagle-import:R0402")
      (libsource (lib "eagle-import") (part "R-0402"))
    )
    (comp (ref "R61")
      (value "DNP")
      (footprint "eagle-import:R0402")
      (libsource (lib "eagle-import") (part "R-0402"))
    )
    (comp (ref "R62")
      (value "DNP")
      (footprint "eagle-import:R0402")
      (libsource (lib "eagle-import") (part "R-0402"))
    )
    (comp (ref "R63")
      (value "DNP")
      (footprint "eagle-import:R0402")
      (libsource (lib "eagle-import") (part "R-0402"))
    )
    (comp (ref "R64")
      (value "DNP")
      (footprint "eagle-import:R0402")
      (libsource (lib "eagle-import") (part "R-0402"))
    )
    (comp (ref "R65")
      (value "10k")
      (footprint "eagle-import:R0402")
      (libsource (lib "eagle-import") (part "R-0402"))
    )
    (comp (ref "R66")
      (value "DNP")
      (footprint "eagle-import:R0402")
      (libsource (lib "eagle-import") (part "R-0402"))
    )
    (comp (ref "R67")
      (value "DNP")
      (footprint "eagle-import:R0402")
      (libsource (lib "eagle-import") (part "R-0402"))
    )
    (comp (ref "R68")
      (value "DNP")
      (footprint "eagle-import:R0402")
      (libsource (lib "eagle-import") (part "R-0402"))
    )
    (comp (ref "R69")
      (value "0R")
      (footprint "eagle-import:R0402")
      (libsource (lib "eagle-import") (part "R-0402"))
    )
    (comp (ref "R70")
      (value "DNP")
      (footprint "eagle-import:R0402")
      (libsource (lib "eagle-import") (part "R-0402"))
    )
    (comp (ref "R71")
      (value "DNP")
      (footprint "eagle-import:R0402")
      (libsource (lib "eagle-import") (part "R-0402"))
    )
    (comp (ref "R72")
      (value "DNP")
      (footprint "eagle-import:R0402")
      (libsource (lib "eagle-import") (part "R-0402"))
    )
    (comp (ref "R73")
      (value "DNP")
      (footprint "eagle-import:R0402")
      (libsource (lib "eagle-import") (part "R-0402"))
    )
    (comp (ref "R74")
      (value "0R")
      (footprint "eagle-import:R0402")
      (libsource (lib "eagle-import") (part "R-0402"))
    )
    (comp (ref "R75")
      (value "0R")
      (footprint "eagle-import:R0402")
      (libsource (lib "eagle-import") (part "R-0402"))
    )
    (comp (ref "R76")
      (value "DNP")
      (footprint "eagle-import:R0402")
      (libsource (lib "eagle-import") (part "R-0402"))
    )
    (comp (ref "R77")
      (value "DNP")
      (footprint "eagle-import:R0402")
      (libsource (lib "eagle-import") (part "R-0402"))
    )
    (comp (ref "R78")
      (value "100k")
      (footprint "eagle-import:R0402")
      (libsource (lib "eagle-import") (part "R-0402"))
    )
    (comp (ref "R79")
      (value "1k")
      (footprint "eagle-import:R0402")
      (libsource (lib "eagle-import") (part "R-0402"))
    )
    (comp (ref "R80")
      (value "10R")
      (footprint "eagle-import:R0402")
      (libsource (lib "eagle-import") (part "R-0402"))
    )
    (comp (ref "R81")
      (value "0R")
      (footprint "eagle-import:R0402")
      (libsource (lib "eagle-import") (part "R-0402"))
    )
    (comp (ref "R82")
      (value "100k")
      (footprint "eagle-import:R0402")
      (libsource (lib "eagle-import") (part "R-0402"))
    )
    (comp (ref "R83")
      (value "200k_1%")
      (footprint "eagle-import:R0402")
      (libsource (lib "eagle-import") (part "R-0402"))
    )
    (comp (ref "R87")
      (value "200k_1%")
      (footprint "eagle-import:R0402")
      (libsource (lib "eagle-import") (part "R-0402"))
    )
    (comp (ref "S1")
      (value "323030226")
      (footprint "eagle-import:SHIELD_CLIP")
      (libsource (lib "eagle-import") (part "SHIELD_CLIP"))
    )
    (comp (ref "S2")
      (value "323030226")
      (footprint "eagle-import:SHIELD_CLIP")
      (libsource (lib "eagle-import") (part "SHIELD_CLIP"))
    )
    (comp (ref "S3")
      (value "323030226")
      (footprint "eagle-import:SHIELD_CLIP")
      (libsource (lib "eagle-import") (part "SHIELD_CLIP"))
    )
    (comp (ref "S4")
      (value "323030226")
      (footprint "eagle-import:SHIELD_CLIP")
      (libsource (lib "eagle-import") (part "SHIELD_CLIP"))
    )
    (comp (ref "S5")
      (value "323030226")
      (footprint "eagle-import:SHIELD_CLIP")
      (libsource (lib "eagle-import") (part "SHIELD_CLIP"))
    )
    (comp (ref "S6")
      (value "323030226")
      (footprint "eagle-import:SHIELD_CLIP")
      (libsource (lib "eagle-import") (part "SHIELD_CLIP"))
    )
    (comp (ref "TP1")
      (value "TEST-POINT-35")
      (footprint "eagle-import:TP_3535")
      (libsource (lib "eagle-import") (part "TEST-POINT-35"))
    )
    (comp (ref "TP2")
      (value "TEST-POINT-35")
      (footprint "eagle-import:TP_3535")
      (libsource (lib "eagle-import") (part "TEST-POINT-35"))
    )
    (comp (ref "TP3")
      (value "TEST-POINT-35")
      (footprint "eagle-import:TP_3535")
      (libsource (lib "eagle-import") (part "TEST-POINT-35"))
    )
    (comp (ref "TP4")
      (value "TEST-POINT-35")
      (footprint "eagle-import:TP_3535")
      (libsource (lib "eagle-import") (part "TEST-POINT-35"))
    )
    (comp (ref "TP5")
      (value "TEST-POINT-35")
      (footprint "eagle-import:TP_3535")
      (libsource (lib "eagle-import") (part "TEST-POINT-35"))
    )
    (comp (ref "TP6")
      (value "TEST-POINT-35")
      (footprint "eagle-import:TP_3535")
      (libsource (lib "eagle-import") (part "TEST-POINT-35"))
    )
    (comp (ref "TP7")
      (value "TEST-POINT-35")
      (footprint "eagle-import:TP_3535")
      (libsource (lib "eagle-import") (part "TEST-POINT-35"))
    )
    (comp (ref "TP8")
      (value "TEST-POINT-35")
      (footprint "eagle-import:TP_3535")
      (libsource (lib "eagle-import") (part "TEST-POINT-35"))
    )
    (comp (ref "TP9")
      (value "TEST-POINT-35")
      (footprint "eagle-import:TP_3535")
      (libsource (lib "eagle-import") (part "TEST-POINT-35"))
    )
    (comp (ref "TP10")
      (value "TEST-POINT-35")
      (footprint "eagle-import:TP_3535")
      (libsource (lib "eagle-import") (part "TEST-POINT-35"))
    )
    (comp (ref "TP14")
      (value "TEST-POINT-35")
      (footprint "eagle-import:TP_3535")
      (libsource (lib "eagle-import") (part "TEST-POINT-35"))
    )
    (comp (ref "TP15")
      (value "TEST-POINT'4545'")
      (footprint "eagle-import:TP-D45MIL")
      (fields (field (name "PARTNO") "DNP"))
      (libsource (lib "eagle-import") (part "TEST-POINT'4545'"))
    )
    (comp (ref "U1")
      (value "SX1302IMLTRT")
      (footprint "eagle-import:QFN68-0.35-7X7X0.75MM")
      (libsource (lib "eagle-import") (part "TRANSCEIVER-SX1302"))
    )
    (comp (ref "U2")
      (value "HDF866A3-S6")
      (footprint "eagle-import:FILTER6P-1.1-3X3X1.3MM")
      (libsource (lib "eagle-import") (part "FILTER-B39871B3717U410"))
    )
    (comp (ref "U3")
      (value "DNP")
      (footprint "eagle-import:SOT-23-5")
      (libsource (lib "eagle-import") (part "LDO-XC6227C331MR"))
    )
    (comp (ref "U4")
      (value "DNP")
      (footprint "eagle-import:SOT-23-5")
      (libsource (lib "eagle-import") (part "LDO-XC6227C331MR"))
    )
    (comp (ref "U5")
      (value "SX1250IMLTRT")
      (footprint "eagle-import:QFN24G-0.5-4X4MM")
      (libsource (lib "eagle-import") (part "RF-SX1250"))
    )
    (comp (ref "U6")
      (value "MP2161GJ")
      (footprint "eagle-import:TSOT23-8")
      (libsource (lib "eagle-import") (part "PMIC-MP2161'GJ'"))
    )
    (comp (ref "U7")
      (value "SX1250IMLTRT")
      (footprint "eagle-import:QFN24G-0.5-4X4MM")
      (libsource (lib "eagle-import") (part "RF-SX1250"))
    )
    (comp (ref "U8")
      (value "HDF866A3-S6")
      (footprint "eagle-import:FILTER6P-1.1-3X3X1.3MM")
      (libsource (lib "eagle-import") (part "FILTER-B39871B3717U410"))
    )
    (comp (ref "U9")
      (value "SKY66420-11")
      (footprint "eagle-import:MODULE16P-0.5-3X3X0.75MM")
      (libsource (lib "eagle-import") (part "MODULE-RF-SKY66420-11"))
    )
    (comp (ref "U10")
      (value "HDF866A3-S6")
      (footprint "eagle-import:FILTER6P-1.1-3X3X1.3MM")
      (libsource (lib "eagle-import") (part "FILTER-B39871B3717U410"))
    )
    (comp (ref "U11")
      (value "DNP")
      (footprint "eagle-import:QFN24G-0.5-4X4MM")
      (libsource (lib "eagle-import") (part "TRANSCEIVER-SX1261/2"))
    )
    (comp (ref "U12")
      (value "DNP")
      (footprint "eagle-import:UFQFPN32-0.5-5X5MM")
      (libsource (lib "eagle-import") (part "MCU-STM32L412KXU6"))
    )
    (comp (ref "U13")
      (value "STTS751")
      (footprint "eagle-import:UDFN-6L")
      (libsource (lib "eagle-import") (part "SENSOR-STTS751"))
    )
    (comp (ref "X1")
      (value "DSB221SDN")
      (footprint "eagle-import:X4-SMD-2.5X2.0X1.0MM")
      (libsource (lib "eagle-import") (part "CRYSTAL-OSCILLATOR-2520"))
    )
    (comp (ref "X3")
      (value "DNP")
      (footprint "eagle-import:X2-SMD-3.2X1.5X0.55MM")
      (libsource (lib "eagle-import") (part "CRYSTAL-2P-3215"))
    )
  )
  (nets
    (net (code "1") (name "32MHZ") (class "Default")
      (node (ref "R37") (pin "2") (pinfunction "2_2") (pintype "passive"))
      (node (ref "R6") (pin "2") (pinfunction "2_2") (pintype "passive"))
      (node (ref "R9") (pin "2") (pinfunction "2_2") (pintype "passive"))
      (node (ref "X1") (pin "3") (pinfunction "OUT_3") (pintype "bidirectional"))
    )
    (net (code "2") (name "1302_CS") (class "Default")
      (node (ref "R33") (pin "2") (pinfunction "2_2") (pintype "passive"))
      (node (ref "R43") (pin "1") (pinfunction "1_1") (pintype "passive"))
      (node (ref "U1") (pin "1") (pinfunction "HOST_CSN_1") (pintype "bidirectional"))
      (node (ref "U12") (pin "10") (pinfunction "PA4_10") (pintype "bidirectional"))
    )
    (net (code "3") (name "1302_RESET") (class "Default")
      (node (ref "C1") (pin "2") (pinfunction "2_2") (pintype "passive"))
      (node (ref "D7") (pin "-") (pinfunction "-_-") (pintype "passive"))
      (node (ref "R1") (pin "2") (pinfunction "2_2") (pintype "passive"))
      (node (ref "U1") (pin "7") (pinfunction "RESET_7") (pintype "bidirectional"))
      (node (ref "U12") (pin "8") (pinfunction "PA2_8") (pintype "bidirectional"))
    )
    (net (code "4") (name "1302_RESET_HOST") (class "Default")
      (node (ref "D7") (pin "+") (pinfunction "+_+") (pintype "passive"))
      (node (ref "R59") (pin "1") (pinfunction "1_1") (pintype "passive"))
    )
    (net (code "5") (name "CONFIG_OK") (class "Default")
      (node (ref "R31") (pin "1") (pinfunction "1_1") (pintype "passive"))
      (node (ref "U1") (pin "66") (pinfunction "GPIO0_66") (pintype "bidirectional"))
    )
    (net (code "6") (name "DM") (class "Default")
      (node (ref "J1") (pin "36") (pinfunction "36_36") (pintype "bidirectional"))
      (node (ref "R66") (pin "1") (pinfunction "1_1") (pintype "passive"))
    )
    (net (code "7") (name "DP") (class "Default")
      (node (ref "J1") (pin "38") (pinfunction "38_38") (pintype "bidirectional"))
      (node (ref "R64") (pin "1") (pinfunction "1_1") (pintype "passive"))
    )
    (net (code "8") (name "FEM_CS") (class "Default")
      (node (ref "R14") (pin "2") (pinfunction "2_2") (pintype "passive"))
      (node (ref "R34") (pin "1") (pinfunction "1_1") (pintype "passive"))
      (node (ref "U1") (pin "10") (pinfunction "RADIO_CTRL0_10") (pintype "bidirectional"))
      (node (ref "U3") (pin "3") (pinfunction "CE_3") (pintype "bidirectional"))
    )
    (net (code "9") (name "FEM_PA_ON") (class "Default")
      (node (ref "R15") (pin "2") (pinfunction "2_2") (pintype "passive"))
      (node (ref "U1") (pin "16") (pinfunction "RADIO_CTRL4_16") (pintype "bidirectional"))
    )
    (net (code "10") (name "GND_POWER") (class "Default")
      (node (ref "ANT1") (pin "GND1") (pinfunction "GND1_GND1") (pintype "bidirectional"))
      (node (ref "ANT1") (pin "GND2") (pinfunction "GND2_GND2") (pintype "bidirectional"))
      (node (ref "ANT2") (pin "GND1") (pinfunction "GND1_GND1") (pintype "bidirectional"))
      (node (ref "ANT2") (pin "GND2") (pinfunction "GND2_GND2") (pintype "bidirectional"))
      (node (ref "C12") (pin "1") (pinfunction "1_1") (pintype "passive"))
      (node (ref "C13") (pin "1") (pinfunction "1_1") (pintype "passive"))
      (node (ref "C15") (pin "1") (pinfunction "1_1") (pintype "passive"))
      (node (ref "C16") (pin "1") (pinfunction "1_1") (pintype "passive"))
      (node (ref "C17") (pin "1") (pinfunction "1_1") (pintype "passive"))
      (node (ref "C18") (pin "1") (pinfunction "1_1") (pintype "passive"))
      (node (ref "C19") (pin "1") (pinfunction "1_1") (pintype "passive"))
      (node (ref "C2") (pin "1") (pinfunction "1_1") (pintype "passive"))
      (node (ref "C20") (pin "1") (pinfunction "1_1") (pintype "passive"))
      (node (ref "C21") (pin "1") (pinfunction "1_1") (pintype "passive"))
      (node (ref "C22") (pin "1") (pinfunction "1_1") (pintype "passive"))
      (node (ref "C23") (pin "1") (pinfunction "1_1") (pintype "passive"))
      (node (ref "C24") (pin "1") (pinfunction "1_1") (pintype "passive"))
      (node (ref "C25") (pin "1") (pinfunction "1_1") (pintype "passive"))
      (node (ref "C26") (pin "1") (pinfunction "1_1") (pintype "passive"))
      (node (ref "C27") (pin "1") (pinfunction "1_1") (pintype "passive"))
      (node (ref "C28") (pin "1") (pinfunction "1_1") (pintype "passive"))
      (node (ref "C29") (pin "1") (pinfunction "1_1") (pintype "passive"))
      (node (ref "C3") (pin "1") (pinfunction "1_1") (pintype "passive"))
      (node (ref "C30") (pin "1") (pinfunction "1_1") (pintype "passive"))
      (node (ref "C31") (pin "1") (pinfunction "1_1") (pintype "passive"))
      (node (ref "C32") (pin "1") (pinfunction "1_1") (pintype "passive"))
      (node (ref "C33") (pin "1") (pinfunction "1_1") (pintype "passive"))
      (node (ref "C34") (pin "1") (pinfunction "1_1") (pintype "passive"))
      (node (ref "C35") (pin "1") (pinfunction "1_1") (pintype "passive"))
      (node (ref "C36") (pin "1") (pinfunction "1_1") (pintype "passive"))
      (node (ref "C37") (pin "1") (pinfunction "1_1") (pintype "passive"))
      (node (ref "C39") (pin "1") (pinfunction "1_1") (pintype "passive"))
      (node (ref "C40") (pin "1") (pinfunction "1_1") (pintype "passive"))
      (node (ref "C41") (pin "1") (pinfunction "1_1") (pintype "passive"))
      (node (ref "C42") (pin "1") (pinfunction "1_1") (pintype "passive"))
      (node (ref "C43") (pin "1") (pinfunction "1_1") (pintype "passive"))
      (node (ref "C44") (pin "1") (pinfunction "1_1") (pintype "passive"))
      (node (ref "C45") (pin "1") (pinfunction "1_1") (pintype "passive"))
      (node (ref "C46") (pin "1") (pinfunction "1_1") (pintype "passive"))
      (node (ref "C47") (pin "1") (pinfunction "1_1") (pintype "passive"))
      (node (ref "C48") (pin "1") (pinfunction "1_1") (pintype "passive"))
      (node (ref "C49") (pin "1") (pinfunction "1_1") (pintype "passive"))
      (node (ref "C5") (pin "1") (pinfunction "1_1") (pintype "passive"))
      (node (ref "C50") (pin "1") (pinfunction "1_1") (pintype "passive"))
      (node (ref "C51") (pin "1") (pinfunction "1_1") (pintype "passive"))
      (node (ref "C52") (pin "1") (pinfunction "1_1") (pintype "passive"))
      (node (ref "C55") (pin "1") (pinfunction "1_1") (pintype "passive"))
      (node (ref "C56") (pin "1") (pinfunction "1_1") (pintype "passive"))
      (node (ref "C57") (pin "1") (pinfunction "1_1") (pintype "passive"))
      (node (ref "C58") (pin "1") (pinfunction "1_1") (pintype "passive"))
      (node (ref "C60") (pin "2") (pinfunction "2_2") (pintype "passive"))
      (node (ref "C61") (pin "2") (pinfunction "2_2") (pintype "passive"))
      (node (ref "C62") (pin "1") (pinfunction "1_1") (pintype "passive"))
      (node (ref "C63") (pin "2") (pinfunction "2_2") (pintype "passive"))
      (node (ref "C65") (pin "2") (pinfunction "2_2") (pintype "passive"))
      (node (ref "C67") (pin "2") (pinfunction "2_2") (pintype "passive"))
      (node (ref "C69") (pin "1") (pinfunction "1_1") (pintype "passive"))
      (node (ref "C7") (pin "1") (pinfunction "1_1") (pintype "passive"))
      (node (ref "C70") (pin "1") (pinfunction "1_1") (pintype "passive"))
      (node (ref "C71") (pin "1") (pinfunction "1_1") (pintype "passive"))
      (node (ref "C72") (pin "1") (pinfunction "1_1") (pintype "passive"))
      (node (ref "C73") (pin "2") (pinfunction "2_2") (pintype "passive"))
      (node (ref "C74") (pin "2") (pinfunction "2_2") (pintype "passive"))
      (node (ref "C76") (pin "1") (pinfunction "1_1") (pintype "passive"))
      (node (ref "C77") (pin "2") (pinfunction "2_2") (pintype "passive"))
      (node (ref "C78") (pin "2") (pinfunction "2_2") (pintype "passive"))
      (node (ref "C80") (pin "1") (pinfunction "1_1") (pintype "passive"))
      (node (ref "C81") (pin "2") (pinfunction "2_2") (pintype "passive"))
      (node (ref "C82") (pin "2") (pinfunction "2_2") (pintype "passive"))
      (node (ref "C83") (pin "1") (pinfunction "1_1") (pintype "passive"))
      (node (ref "C84") (pin "2") (pinfunction "2_2") (pintype "passive"))
      (node (ref "C85") (pin "1") (pinfunction "1_1") (pintype "passive"))
      (node (ref "C86") (pin "1") (pinfunction "1_1") (pintype "passive"))
      (node (ref "C87") (pin "1") (pinfunction "1_1") (pintype "passive"))
      (node (ref "C88") (pin "1") (pinfunction "1_1") (pintype "passive"))
      (node (ref "C89") (pin "1") (pinfunction "1_1") (pintype "passive"))
      (node (ref "C9") (pin "1") (pinfunction "1_1") (pintype "passive"))
      (node (ref "C90") (pin "1") (pinfunction "1_1") (pintype "passive"))
      (node (ref "C92") (pin "1") (pinfunction "1_1") (pintype "passive"))
      (node (ref "D1") (pin "-") (pinfunction "-_-") (pintype "passive"))
      (node (ref "D2") (pin "-") (pinfunction "-_-") (pintype "passive"))
      (node (ref "D3") (pin "-") (pinfunction "-_-") (pintype "passive"))
      (node (ref "D4") (pin "-") (pinfunction "-_-") (pintype "passive"))
      (node (ref "D5") (pin "1") (pinfunction "1_1") (pintype "bidirectional"))
      (node (ref "D6") (pin "1") (pinfunction "1_1") (pintype "bidirectional"))
      (node (ref "J1") (pin "15") (pinfunction "GND_15") (pintype "bidirectional"))
      (node (ref "J1") (pin "18") (pinfunction "GND_18") (pintype "bidirectional"))
      (node (ref "J1") (pin "21") (pinfunction "GND_21") (pintype "bidirectional"))
      (node (ref "J1") (pin "26") (pinfunction "GND_26") (pintype "bidirectional"))
      (node (ref "J1") (pin "27") (pinfunction "GND_27") (pintype "bidirectional"))
      (node (ref "J1") (pin "29") (pinfunction "GND_29") (pintype "bidirectional"))
      (node (ref "J1") (pin "34") (pinfunction "GND_34") (pintype "bidirectional"))
      (node (ref "J1") (pin "35") (pinfunction "GND_35") (pintype "bidirectional"))
      (node (ref "J1") (pin "37") (pinfunction "GND_37") (pintype "bidirectional"))
      (node (ref "J1") (pin "4") (pinfunction "GND_4") (pintype "bidirectional"))
      (node (ref "J1") (pin "40") (pinfunction "GND_40") (pintype "bidirectional"))
      (node (ref "J1") (pin "43") (pinfunction "GND_43") (pintype "bidirectional"))
      (node (ref "J1") (pin "50") (pinfunction "GND_50") (pintype "bidirectional"))
      (node (ref "J1") (pin "9") (pinfunction "GND_9") (pintype "bidirectional"))
      (node (ref "J1") (pin "S1") (pinfunction "GND_S1") (pintype "bidirectional"))
      (node (ref "J1") (pin "S2") (pinfunction "GND_S2") (pintype "bidirectional"))
      (node (ref "Q10") (pin "2") (pinfunction "S_2") (pintype "passive"))
      (node (ref "R1") (pin "1") (pinfunction "1_1") (pintype "passive"))
      (node (ref "R11") (pin "1") (pinfunction "1_1") (pintype "passive"))
      (node (ref "R12") (pin "1") (pinfunction "1_1") (pintype "passive"))
      (node (ref "R17") (pin "2") (pinfunction "2_2") (pintype "passive"))
      (node (ref "R4") (pin "1") (pinfunction "1_1") (pintype "passive"))
      (node (ref "R53") (pin "1") (pinfunction "1_1") (pintype "passive"))
      (node (ref "R53") (pin "2") (pinfunction "2_2") (pintype "passive"))
      (node (ref "R54") (pin "1") (pinfunction "1_1") (pintype "passive"))
      (node (ref "R54") (pin "2") (pinfunction "2_2") (pintype "passive"))
      (node (ref "R55") (pin "1") (pinfunction "1_1") (pintype "passive"))
      (node (ref "R55") (pin "2") (pinfunction "2_2") (pintype "passive"))
      (node (ref "R57") (pin "2") (pinfunction "2_2") (pintype "passive"))
      (node (ref "R73") (pin "1") (pinfunction "1_1") (pintype "passive"))
      (node (ref "R74") (pin "1") (pinfunction "1_1") (pintype "passive"))
      (node (ref "R74") (pin "2") (pinfunction "2_2") (pintype "passive"))
      (node (ref "R87") (pin "1") (pinfunction "1_1") (pintype "passive"))
      (node (ref "S1") (pin "S1") (pinfunction "S1_S1") (pintype "bidirectional"))
      (node (ref "S1") (pin "S2") (pinfunction "S1_S2") (pintype "bidirectional"))
      (node (ref "S1") (pin "S3") (pinfunction "S1_S3") (pintype "bidirectional"))
      (node (ref "S1") (pin "S4") (pinfunction "S1_S4") (pintype "bidirectional"))
      (node (ref "S1") (pin "S5") (pinfunction "S1_S5") (pintype "bidirectional"))
      (node (ref "S2") (pin "S1") (pinfunction "S1_S1") (pintype "bidirectional"))
      (node (ref "S2") (pin "S2") (pinfunction "S1_S2") (pintype "bidirectional"))
      (node (ref "S2") (pin "S3") (pinfunction "S1_S3") (pintype "bidirectional"))
      (node (ref "S2") (pin "S4") (pinfunction "S1_S4") (pintype "bidirectional"))
      (node (ref "S2") (pin "S5") (pinfunction "S1_S5") (pintype "bidirectional"))
      (node (ref "S3") (pin "S1") (pinfunction "S1_S1") (pintype "bidirectional"))
      (node (ref "S3") (pin "S2") (pinfunction "S1_S2") (pintype "bidirectional"))
      (node (ref "S3") (pin "S3") (pinfunction "S1_S3") (pintype "bidirectional"))
      (node (ref "S3") (pin "S4") (pinfunction "S1_S4") (pintype "bidirectional"))
      (node (ref "S3") (pin "S5") (pinfunction "S1_S5") (pintype "bidirectional"))
      (node (ref "S4") (pin "S1") (pinfunction "S1_S1") (pintype "bidirectional"))
      (node (ref "S4") (pin "S2") (pinfunction "S1_S2") (pintype "bidirectional"))
      (node (ref "S4") (pin "S3") (pinfunction "S1_S3") (pintype "bidirectional"))
      (node (ref "S4") (pin "S4") (pinfunction "S1_S4") (pintype "bidirectional"))
      (node (ref "S4") (pin "S5") (pinfunction "S1_S5") (pintype "bidirectional"))
      (node (ref "S5") (pin "S1") (pinfunction "S1_S1") (pintype "bidirectional"))
      (node (ref "S5") (pin "S2") (pinfunction "S1_S2") (pintype "bidirectional"))
      (node (ref "S5") (pin "S3") (pinfunction "S1_S3") (pintype "bidirectional"))
      (node (ref "S5") (pin "S4") (pinfunction "S1_S4") (pintype "bidirectional"))
      (node (ref "S5") (pin "S5") (pinfunction "S1_S5") (pintype "bidirectional"))
      (node (ref "S6") (pin "S1") (pinfunction "S1_S1") (pintype "bidirectional"))
      (node (ref "S6") (pin "S2") (pinfunction "S1_S2") (pintype "bidirectional"))
      (node (ref "S6") (pin "S3") (pinfunction "S1_S3") (pintype "bidirectional"))
      (node (ref "S6") (pin "S4") (pinfunction "S1_S4") (pintype "bidirectional"))
      (node (ref "S6") (pin "S5") (pinfunction "S1_S5") (pintype "bidirectional"))
      (node (ref "TP3") (pin "T") (pinfunction "T_T") (pintype "bidirectional"))
      (node (ref "U1") (pin "15") (pinfunction "GND_15") (pintype "bidirectional"))
      (node (ref "U1") (pin "24") (pinfunction "GND_24") (pintype "bidirectional"))
      (node (ref "U1") (pin "25") (pinfunction "GND_25") (pintype "bidirectional"))
      (node (ref "U1") (pin "39") (pinfunction "GND_39") (pintype "bidirectional"))
      (node (ref "U1") (pin "46") (pinfunction "GND_46") (pintype "bidirectional"))
      (node (ref "U1") (pin "55") (pinfunction "GND_55") (pintype "bidirectional"))
      (node (ref "U1") (pin "6") (pinfunction "GND_6") (pintype "bidirectional"))
      (node (ref "U1") (pin "62") (pinfunction "GND_62") (pintype "bidirectional"))
      (node (ref "U1") (pin "69") (pinfunction "GND_69") (pintype "bidirectional"))
      (node (ref "U1") (pin "9") (pinfunction "GND_9") (pintype "bidirectional"))
      (node (ref "U10") (pin "1") (pinfunction "GND_1") (pintype "bidirectional"))
      (node (ref "U10") (pin "3") (pinfunction "GND_3") (pintype "bidirectional"))
      (node (ref "U10") (pin "4") (pinfunction "GND_4") (pintype "bidirectional"))
      (node (ref "U10") (pin "6") (pinfunction "GND_6") (pintype "bidirectional"))
      (node (ref "U11") (pin "2") (pinfunction "GND_2") (pintype "bidirectional"))
      (node (ref "U11") (pin "20") (pinfunction "GND_20") (pintype "bidirectional"))
      (node (ref "U11") (pin "5") (pinfunction "GND_5") (pintype "bidirectional"))
      (node (ref "U11") (pin "8") (pinfunction "GND_8") (pintype "bidirectional"))
      (node (ref "U11") (pin "PAD") (pinfunction "PAD_PAD") (pintype "bidirectional"))
      (node (ref "U12") (pin "16") (pinfunction "VSS_16") (pintype "bidirectional"))
      (node (ref "U12") (pin "32") (pinfunction "VSS_32") (pintype "bidirectional"))
      (node (ref "U12") (pin "PAD") (pinfunction "PAD_PAD") (pintype "bidirectional"))
      (node (ref "U13") (pin "4") (pinfunction "ADDR/~{THERM}_4") (pintype "bidirectional"))
      (node (ref "U13") (pin "5") (pinfunction "GND_5") (pintype "bidirectional"))
      (node (ref "U2") (pin "1") (pinfunction "GND_1") (pintype "bidirectional"))
      (node (ref "U2") (pin "3") (pinfunction "GND_3") (pintype "bidirectional"))
      (node (ref "U2") (pin "4") (pinfunction "GND_4") (pintype "bidirectional"))
      (node (ref "U2") (pin "6") (pinfunction "GND_6") (pintype "bidirectional"))
      (node (ref "U3") (pin "2") (pinfunction "VSS_2") (pintype "bidirectional"))
      (node (ref "U4") (pin "2") (pinfunction "VSS_2") (pintype "bidirectional"))
      (node (ref "U5") (pin "20") (pinfunction "GND_20") (pintype "bidirectional"))
      (node (ref "U5") (pin "7") (pinfunction "GND_7") (pintype "bidirectional"))
      (node (ref "U5") (pin "PAD") (pinfunction "PAD_PAD") (pintype "bidirectional"))
      (node (ref "U6") (pin "4") (pinfunction "PGND_4") (pintype "bidirectional"))
      (node (ref "U6") (pin "6") (pinfunction "AGND_6") (pintype "bidirectional"))
      (node (ref "U7") (pin "20") (pinfunction "GND_20") (pintype "bidirectional"))
      (node (ref "U7") (pin "7") (pinfunction "GND_7") (pintype "bidirectional"))
      (node (ref "U7") (pin "PAD") (pinfunction "PAD_PAD") (pintype "bidirectional"))
      (node (ref "U8") (pin "1") (pinfunction "GND_1") (pintype "bidirectional"))
      (node (ref "U8") (pin "3") (pinfunction "GND_3") (pintype "bidirectional"))
      (node (ref "U8") (pin "4") (pinfunction "GND_4") (pintype "bidirectional"))
      (node (ref "U8") (pin "6") (pinfunction "GND_6") (pintype "bidirectional"))
      (node (ref "U9") (pin "10") (pinfunction "GND_10") (pintype "bidirectional"))
      (node (ref "U9") (pin "12") (pinfunction "GND_12") (pintype "bidirectional"))
      (node (ref "U9") (pin "17") (pinfunction "EPAD_17") (pintype "bidirectional"))
      (node (ref "X1") (pin "2") (pinfunction "GND_2") (pintype "bidirectional"))
    )
    (net (code "11") (name "HOST_CS0") (class "Default")
      (node (ref "J1") (pin "51") (pinfunction "51_51") (pintype "bidirectional"))
      (node (ref "R43") (pin "2") (pinfunction "2_2") (pintype "passive"))
    )
    (net (code "12") (name "HOST_CS1") (class "Default")
      (node (ref "J1") (pin "25") (pinfunction "25_25") (pintype "bidirectional"))
      (node (ref "R51") (pin "2") (pinfunction "2_2") (pintype "passive"))
    )
    (net (code "13") (name "HOST_IO1") (class "Default")
      (node (ref "J1") (pin "33") (pinfunction "33_33") (pintype "bidirectional"))
      (node (ref "R61") (pin "2") (pinfunction "2_2") (pintype "passive"))
    )
    (net (code "14") (name "HOST_IO2") (class "Default")
      (node (ref "J1") (pin "31") (pinfunction "31_31") (pintype "bidirectional"))
      (node (ref "R63") (pin "2") (pinfunction "2_2") (pintype "passive"))
    )
    (net (code "15") (name "HOST_IO3") (class "Default")
      (node (ref "J1") (pin "23") (pinfunction "23_23") (pintype "bidirectional"))
    )
    (net (code "16") (name "HOST_IO4") (class "Default")
      (node (ref "J1") (pin "8") (pinfunction "8_8") (pintype "bidirectional"))
      (node (ref "R67") (pin "2") (pinfunction "2_2") (pintype "passive"))
    )
    (net (code "17") (name "HOST_IO5") (class "Default")
      (node (ref "J1") (pin "10") (pinfunction "10_10") (pintype "bidirectional"))
      (node (ref "R60") (pin "2") (pinfunction "2_2") (pintype "passive"))
    )
    (net (code "18") (name "HOST_IO6") (class "Default")
      (node (ref "J1") (pin "12") (pinfunction "12_12") (pintype "bidirectional"))
    )
    (net (code "19") (name "HOST_MISO") (class "Default")
      (node (ref "R39") (pin "1") (pinfunction "1_1") (pintype "passive"))
      (node (ref "R44") (pin "2") (pinfunction "2_2") (pintype "passive"))
    )
    (net (code "20") (name "HOST_MOSI") (class "Default")
      (node (ref "J1") (pin "49") (pinfunction "49_49") (pintype "bidirectional"))
      (node (ref "R46") (pin "2") (pinfunction "2_2") (pintype "passive"))
    )
    (net (code "21") (name "HOST_RST") (class "Default")
      (node (ref "J1") (pin "22") (pinfunction "22_22") (pintype "bidirectional"))
      (node (ref "R59") (pin "2") (pinfunction "2_2") (pintype "passive"))
      (node (ref "R77") (pin "2") (pinfunction "2_2") (pintype "passive"))
    )
    (net (code "22") (name "HOST_SCK") (class "Default")
      (node (ref "J1") (pin "45") (pinfunction "45_45") (pintype "bidirectional"))
      (node (ref "R49") (pin "2") (pinfunction "2_2") (pintype "passive"))
    )
    (net (code "23") (name "I2C_SCL") (class "Default")
      (node (ref "R68") (pin "2") (pinfunction "2_2") (pintype "passive"))
      (node (ref "R76") (pin "1") (pinfunction "1_1") (pintype "passive"))
      (node (ref "R81") (pin "1") (pinfunction "1_1") (pintype "passive"))
      (node (ref "U12") (pin "29") (pinfunction "PB6_29") (pintype "bidirectional"))
      (node (ref "U13") (pin "1") (pinfunction "SCL_1") (pintype "bidirectional"))
    )
    (net (code "24") (name "I2C_SDA") (class "Default")
      (node (ref "R58") (pin "2") (pinfunction "2_2") (pintype "passive"))
      (node (ref "R70") (pin "1") (pinfunction "1_1") (pintype "passive"))
      (node (ref "R75") (pin "1") (pinfunction "1_1") (pintype "passive"))
      (node (ref "U12") (pin "30") (pinfunction "PB7_30") (pintype "bidirectional"))
      (node (ref "U13") (pin "6") (pinfunction "SDA_6") (pintype "bidirectional"))
    )
    (net (code "25") (name "MCU_RESET") (class "Default")
      (node (ref "C85") (pin "2") (pinfunction "2_2") (pintype "passive"))
      (node (ref "R71") (pin "2") (pinfunction "2_2") (pintype "passive"))
      (node (ref "R77") (pin "1") (pinfunction "1_1") (pintype "passive"))
      (node (ref "TP5") (pin "T") (pinfunction "T_T") (pintype "bidirectional"))
      (node (ref "U12") (pin "4") (pinfunction "NRST_4") (pintype "bidirectional"))
    )
    (net (code "26") (name "MISO") (class "Default")
      (node (ref "R44") (pin "1") (pinfunction "1_1") (pintype "passive"))
      (node (ref "R45") (pin "1") (pinfunction "1_1") (pintype "passive"))
      (node (ref "U1") (pin "2") (pinfunction "HOST_MISO_2") (pintype "bidirectional"))
      (node (ref "U11") (pin "16") (pinfunction "MISO_16") (pintype "bidirectional"))
    )
    (net (code "27") (name "MISO_A") (class "Default")
      (node (ref "U1") (pin "42") (pinfunction "RADIO_A_MISO_42") (pintype "bidirectional"))
      (node (ref "U5") (pin "16") (pinfunction "MISO_16") (pintype "bidirectional"))
    )
    (net (code "28") (name "MISO_B") (class "Default")
      (node (ref "U1") (pin "33") (pinfunction "RADIO_B_MISO_33") (pintype "bidirectional"))
      (node (ref "U7") (pin "16") (pinfunction "MISO_16") (pintype "bidirectional"))
    )
    (net (code "29") (name "MOSI") (class "Default")
      (node (ref "R40") (pin "2") (pinfunction "2_2") (pintype "passive"))
      (node (ref "R46") (pin "1") (pinfunction "1_1") (pintype "passive"))
      (node (ref "R48") (pin "1") (pinfunction "1_1") (pintype "passive"))
      (node (ref "R5") (pin "2") (pinfunction "2_2") (pintype "passive"))
    )
    (net (code "30") (name "MOSI_A") (class "Default")
      (node (ref "U1") (pin "67") (pinfunction "RADIO_A_MOSI_67") (pintype "bidirectional"))
      (node (ref "U5") (pin "17") (pinfunction "MOSI_17") (pintype "bidirectional"))
    )
    (net (code "31") (name "MOSI_B") (class "Default")
      (node (ref "U1") (pin "19") (pinfunction "RADIO_B_MOSI_19") (pintype "bidirectional"))
      (node (ref "U7") (pin "17") (pinfunction "MOSI_17") (pintype "bidirectional"))
    )
    (net (code "32") (name "Net-(ANT1-PadD)") (class "Default")
      (node (ref "ANT1") (pin "D") (pinfunction "D_D") (pintype "bidirectional"))
      (node (ref "C64") (pin "2") (pinfunction "2_2") (pintype "passive"))
      (node (ref "D5") (pin "2") (pinfunction "2_2") (pintype "bidirectional"))
    )
    (net (code "33") (name "Net-(ANT2-PadD)") (class "Default")
      (node (ref "ANT2") (pin "D") (pinfunction "D_D") (pintype "bidirectional"))
      (node (ref "C79") (pin "2") (pinfunction "2_2") (pintype "passive"))
      (node (ref "D6") (pin "2") (pinfunction "2_2") (pintype "bidirectional"))
    )
    (net (code "34") (name "Net-(C1-Pad1)") (class "Default")
      (node (ref "C1") (pin "1") (pinfunction "1_1") (pintype "passive"))
      (node (ref "R80") (pin "1") (pinfunction "1_1") (pintype "passive"))
    )
    (net (code "35") (name "Net-(C4-Pad1)") (class "Default")
      (node (ref "C4") (pin "1") (pinfunction "1_1") (pintype "passive"))
      (node (ref "C8") (pin "2") (pinfunction "2_2") (pintype "passive"))
      (node (ref "R12") (pin "2") (pinfunction "2_2") (pintype "passive"))
    )
    (net (code "36") (name "Net-(C14-Pad2)") (class "Default")
      (node (ref "C14") (pin "2") (pinfunction "2_2") (pintype "passive"))
      (node (ref "R6") (pin "1") (pinfunction "1_1") (pintype "passive"))
    )
    (net (code "37") (name "Net-(C38-Pad2)") (class "Default")
      (node (ref "C38") (pin "2") (pinfunction "2_2") (pintype "passive"))
      (node (ref "R9") (pin "1") (pinfunction "1_1") (pintype "passive"))
    )
    (net (code "38") (name "Net-(C53-Pad2)") (class "Default")
      (node (ref "C53") (pin "2") (pinfunction "2_2") (pintype "passive"))
      (node (ref "C54") (pin "1") (pinfunction "1_1") (pintype "passive"))
      (node (ref "C7") (pin "2") (pinfunction "2_2") (pintype "passive"))
      (node (ref "L10") (pin "2") (pinfunction "2_2") (pintype "passive"))
    )
    (net (code "39") (name "Net-(C54-Pad2)") (class "Default")
      (node (ref "C54") (pin "2") (pinfunction "2_2") (pintype "passive"))
      (node (ref "L11") (pin "1") (pinfunction "1_1") (pintype "passive"))
    )
    (net (code "40") (name "Net-(C56-Pad2)") (class "Default")
      (node (ref "C56") (pin "2") (pinfunction "2_2") (pintype "passive"))
      (node (ref "C57") (pin "2") (pinfunction "2_2") (pintype "passive"))
      (node (ref "L16") (pin "1") (pinfunction "1_1") (pintype "passive"))
      (node (ref "L8") (pin "2") (pinfunction "2_2") (pintype "passive"))
    )
    (net (code "41") (name "Net-(C59-Pad1)") (class "Default")
      (node (ref "C59") (pin "1") (pinfunction "1_1") (pintype "passive"))
      (node (ref "C91") (pin "2") (pinfunction "2_2") (pintype "passive"))
    )
    (net (code "42") (name "Net-(C61-Pad1)") (class "Default")
      (node (ref "C61") (pin "1") (pinfunction "1_1") (pintype "passive"))
      (node (ref "C91") (pin "1") (pinfunction "1_1") (pintype "passive"))
      (node (ref "L17") (pin "2") (pinfunction "2_2") (pintype "passive"))
      (node (ref "L24") (pin "1") (pinfunction "1_1") (pintype "passive"))
    )
    (net (code "43") (name "Net-(C64-Pad1)") (class "Default")
      (node (ref "C64") (pin "1") (pinfunction "1_1") (pintype "passive"))
      (node (ref "C82") (pin "1") (pinfunction "1_1") (pintype "passive"))
      (node (ref "L24") (pin "2") (pinfunction "2_2") (pintype "passive"))
    )
    (net (code "44") (name "Net-(C66-Pad2)") (class "Default")
      (node (ref "C66") (pin "2") (pinfunction "2_2") (pintype "passive"))
      (node (ref "R37") (pin "1") (pinfunction "1_1") (pintype "passive"))
    )
    (net (code "45") (name "Net-(C68-Pad1)") (class "Default")
      (node (ref "C68") (pin "1") (pinfunction "1_1") (pintype "passive"))
      (node (ref "C74") (pin "1") (pinfunction "1_1") (pintype "passive"))
      (node (ref "C75") (pin "2") (pinfunction "2_2") (pintype "passive"))
    )
    (net (code "46") (name "Net-(C77-Pad1)") (class "Default")
      (node (ref "C77") (pin "1") (pinfunction "1_1") (pintype "passive"))
      (node (ref "L21") (pin "1") (pinfunction "1_1") (pintype "passive"))
      (node (ref "R62") (pin "2") (pinfunction "2_2") (pintype "passive"))
    )
    (net (code "47") (name "Net-(C78-Pad1)") (class "Default")
      (node (ref "C78") (pin "1") (pinfunction "1_1") (pintype "passive"))
      (node (ref "C79") (pin "1") (pinfunction "1_1") (pintype "passive"))
      (node (ref "L21") (pin "2") (pinfunction "2_2") (pintype "passive"))
    )
    (net (code "48") (name "Net-(D1-Pad+)") (class "Default")
      (node (ref "D1") (pin "+") (pinfunction "+_+") (pintype "passive"))
      (node (ref "R30") (pin "2") (pinfunction "2_2") (pintype "passive"))
    )
    (net (code "49") (name "Net-(D2-Pad+)") (class "Default")
      (node (ref "D2") (pin "+") (pinfunction "+_+") (pintype "passive"))
      (node (ref "R31") (pin "2") (pinfunction "2_2") (pintype "passive"))
    )
    (net (code "50") (name "Net-(D3-Pad+)") (class "Default")
      (node (ref "D3") (pin "+") (pinfunction "+_+") (pintype "passive"))
      (node (ref "R32") (pin "2") (pinfunction "2_2") (pintype "passive"))
    )
    (net (code "51") (name "Net-(D4-Pad+)") (class "Default")
      (node (ref "D4") (pin "+") (pinfunction "+_+") (pintype "passive"))
      (node (ref "R47") (pin "2") (pinfunction "2_2") (pintype "passive"))
    )
    (net (code "52") (name "Net-(J1-Pad14)") (class "Default")
      (node (ref "J1") (pin "14") (pinfunction "14_14") (pintype "bidirectional"))
      (node (ref "R76") (pin "2") (pinfunction "2_2") (pintype "passive"))
    )
    (net (code "53") (name "Net-(J1-Pad16)") (class "Default")
      (node (ref "J1") (pin "16") (pinfunction "16_16") (pintype "bidirectional"))
      (node (ref "R70") (pin "2") (pinfunction "2_2") (pintype "passive"))
    )
    (net (code "54") (name "Net-(J1-Pad30)") (class "Default")
      (node (ref "J1") (pin "30") (pinfunction "30_30") (pintype "bidirectional"))
      (node (ref "R81") (pin "2") (pinfunction "2_2") (pintype "passive"))
    )
    (net (code "55") (name "Net-(J1-Pad32)") (class "Default")
      (node (ref "J1") (pin "32") (pinfunction "32_32") (pintype "bidirectional"))
      (node (ref "R75") (pin "2") (pinfunction "2_2") (pintype "passive"))
    )
    (net (code "56") (name "Net-(J1-Pad47)") (class "Default")
      (node (ref "J1") (pin "47") (pinfunction "47_47") (pintype "bidirectional"))
      (node (ref "R39") (pin "2") (pinfunction "2_2") (pintype "passive"))
    )
    (net (code "57") (name "Net-(Q10-D)") (class "Default")
      (node (ref "Q10") (pin "3") (pinfunction "D_3") (pintype "passive"))
      (node (ref "Q8") (pin "1") (pinfunction "G_1") (pintype "passive"))
      (node (ref "R78") (pin "2") (pinfunction "2_2") (pintype "passive"))
    )
    (net (code "58") (name "Net-(Q10-G)") (class "Default")
      (node (ref "C92") (pin "2") (pinfunction "2_2") (pintype "passive"))
      (node (ref "Q10") (pin "1") (pinfunction "G_1") (pintype "passive"))
      (node (ref "R79") (pin "2") (pinfunction "2_2") (pintype "passive"))
    )
    (net (code "59") (name "Net-(U1-HOST_MOSI)") (class "Default")
      (node (ref "R5") (pin "1") (pinfunction "1_1") (pintype "passive"))
      (node (ref "U1") (pin "3") (pinfunction "HOST_MOSI_3") (pintype "bidirectional"))
    )
    (net (code "60") (name "Net-(U1-HOST_SCK)") (class "Default")
      (node (ref "R10") (pin "1") (pinfunction "1_1") (pintype "passive"))
      (node (ref "U1") (pin "4") (pinfunction "HOST_SCK_4") (pintype "bidirectional"))
    )
    (net (code "61") (name "Net-(U1-RADIO_A_CLK_I)") (class "Default")
      (node (ref "R25") (pin "1") (pinfunction "1_1") (pintype "passive"))
      (node (ref "U1") (pin "43") (pinfunction "RADIO_A_CLK_I_43") (pintype "bidirectional"))
    )
    (net (code "62") (name "Net-(U1-RADIO_A_IQ0)") (class "Default")
      (node (ref "R26") (pin "1") (pinfunction "1_1") (pintype "passive"))
      (node (ref "U1") (pin "44") (pinfunction "RADIO_A_IQ0_44") (pintype "bidirectional"))
    )
    (net (code "63") (name "Net-(U1-RADIO_A_IQ1)") (class "Default")
      (node (ref "R27") (pin "1") (pinfunction "1_1") (pintype "passive"))
      (node (ref "U1") (pin "45") (pinfunction "RADIO_A_IQ1_45") (pintype "bidirectional"))
    )
    (net (code "64") (name "Net-(U1-RADIO_A_IQ2)") (class "Default")
      (node (ref "R29") (pin "1") (pinfunction "1_1") (pintype "passive"))
      (node (ref "U1") (pin "49") (pinfunction "RADIO_A_IQ2_49") (pintype "bidirectional"))
    )
    (net (code "65") (name "Net-(U1-RADIO_A_IQ3)") (class "Default")
      (node (ref "R24") (pin "1") (pinfunction "1_1") (pintype "passive"))
      (node (ref "U1") (pin "41") (pinfunction "RADIO_A_IQ3_41") (pintype "bidirectional"))
    )
    (net (code "66") (name "Net-(U1-RADIO_A_IQ4)") (class "Default")
      (node (ref "R28") (pin "1") (pinfunction "1_1") (pintype "passive"))
      (node (ref "U1") (pin "48") (pinfunction "RADIO_A_IQ4_48") (pintype "bidirectional"))
    )
    (net (code "67") (name "Net-(U1-RADIO_B_CLK_I)") (class "Default")
      (node (ref "R19") (pin "1") (pinfunction "1_1") (pintype "passive"))
      (node (ref "U1") (pin "34") (pinfunction "RADIO_B_CLK_I_34") (pintype "bidirectional"))
    )
    (net (code "68") (name "Net-(U1-RADIO_B_IQ0)") (class "Default")
      (node (ref "R20") (pin "1") (pinfunction "1_1") (pintype "passive"))
      (node (ref "U1") (pin "35") (pinfunction "RADIO_B_IQ0_35") (pintype "bidirectional"))
    )
    (net (code "69") (name "Net-(U1-RADIO_B_IQ1)") (class "Default")
      (node (ref "R21") (pin "1") (pinfunction "1_1") (pintype "passive"))
      (node (ref "U1") (pin "36") (pinfunction "RADIO_B_IQ1_36") (pintype "bidirectional"))
    )
    (net (code "70") (name "Net-(U1-RADIO_B_IQ2)") (class "Default")
      (node (ref "R23") (pin "1") (pinfunction "1_1") (pintype "passive"))
      (node (ref "U1") (pin "38") (pinfunction "RADIO_B_IQ2_38") (pintype "bidirectional"))
    )
    (net (code "71") (name "Net-(U1-RADIO_B_IQ3)") (class "Default")
      (node (ref "R18") (pin "1") (pinfunction "1_1") (pintype "passive"))
      (node (ref "U1") (pin "32") (pinfunction "RADIO_B_IQ3_32") (pintype "bidirectional"))
    )
    (net (code "72") (name "Net-(U1-RADIO_B_IQ4)") (class "Default")
      (node (ref "R22") (pin "1") (pinfunction "1_1") (pintype "passive"))
      (node (ref "U1") (pin "37") (pinfunction "RADIO_B_IQ4_37") (pintype "bidirectional"))
    )
    (net (code "73") (name "Net-(U1-SP_VALID)") (class "Default")
      (node (ref "R17") (pin "1") (pinfunction "1_1") (pintype "passive"))
      (node (ref "U1") (pin "20") (pinfunction "SP_VALID_20") (pintype "bidirectional"))
    )
    (net (code "74") (name "Net-(U2-IN)") (class "Default")
      (node (ref "C11") (pin "1") (pinfunction "1_1") (pintype "passive"))
      (node (ref "R13") (pin "2") (pinfunction "2_2") (pintype "passive"))
      (node (ref "U2") (pin "2") (pinfunction "IN_2") (pintype "bidirectional"))
    )
    (net (code "75") (name "Net-(U2-OUT)") (class "Default")
      (node (ref "C10") (pin "1") (pinfunction "1_1") (pintype "passive"))
      (node (ref "C6") (pin "1") (pinfunction "1_1") (pintype "passive"))
      (node (ref "C75") (pin "1") (pinfunction "1_1") (pintype "passive"))
      (node (ref "R13") (pin "1") (pinfunction "1_1") (pintype "passive"))
      (node (ref "U2") (pin "5") (pinfunction "OUT_5") (pintype "bidirectional"))
    )
    (net (code "76") (name "Net-(U4-CE)") (class "Default")
      (node (ref "R8") (pin "1") (pinfunction "1_1") (pintype "passive"))
      (node (ref "U4") (pin "3") (pinfunction "CE_3") (pintype "bidirectional"))
    )
    (net (code "77") (name "Net-(U5-DCC_SW)") (class "Default")
      (node (ref "L6") (pin "2") (pinfunction "2_2") (pintype "passive"))
      (node (ref "U5") (pin "8") (pinfunction "DCC_SW_8") (pintype "bidirectional"))
    )
    (net (code "78") (name "Net-(U5-VREG)") (class "Default")
      (node (ref "C34") (pin "2") (pinfunction "2_2") (pintype "passive"))
      (node (ref "L6") (pin "1") (pinfunction "1_1") (pintype "passive"))
      (node (ref "L7") (pin "2") (pinfunction "2_2") (pintype "passive"))
      (node (ref "U5") (pin "6") (pinfunction "VREG_6") (pintype "bidirectional"))
    )
    (net (code "79") (name "Net-(U5-VR_PA)") (class "Default")
      (node (ref "C36") (pin "2") (pinfunction "2_2") (pintype "passive"))
      (node (ref "C37") (pin "2") (pinfunction "2_2") (pintype "passive"))
      (node (ref "L9") (pin "2") (pinfunction "2_2") (pintype "passive"))
      (node (ref "U5") (pin "1") (pinfunction "VR_PA_1") (pintype "bidirectional"))
    )
    (net (code "80") (name "Net-(U5-XTA)") (class "Default")
      (node (ref "C14") (pin "1") (pinfunction "1_1") (pintype "passive"))
      (node (ref "U5") (pin "3") (pinfunction "XTA_3") (pintype "bidirectional"))
    )
    (net (code "81") (name "Net-(U6-EN)") (class "Default")
      (node (ref "R82") (pin "2") (pinfunction "2_2") (pintype "passive"))
      (node (ref "U6") (pin "8") (pinfunction "EN_8") (pintype "bidirectional"))
    )
    (net (code "82") (name "Net-(U6-FB)") (class "Default")
      (node (ref "R83") (pin "1") (pinfunction "1_1") (pintype "passive"))
      (node (ref "R87") (pin "2") (pinfunction "2_2") (pintype "passive"))
      (node (ref "U6") (pin "7") (pinfunction "FB_7") (pintype "bidirectional"))
    )
    (net (code "83") (name "Net-(U6-PG)") (class "Default")
      (node (ref "TP15") (pin "T") (pinfunction "T_T") (pintype "bidirectional"))
      (node (ref "U6") (pin "1") (pinfunction "PG_1") (pintype "bidirectional"))
    )
    (net (code "84") (name "Net-(U6-SW)") (class "Default")
      (node (ref "L5") (pin "1") (pinfunction "1_1") (pintype "passive"))
      (node (ref "U6") (pin "3") (pinfunction "SW_3") (pintype "bidirectional"))
    )
    (net (code "85") (name "Net-(U7-DCC_SW)") (class "Default")
      (node (ref "L14") (pin "2") (pinfunction "2_2") (pintype "passive"))
      (node (ref "U7") (pin "8") (pinfunction "DCC_SW_8") (pintype "bidirectional"))
    )
    (net (code "86") (name "Net-(U7-VREG)") (class "Default")
      (node (ref "C46") (pin "2") (pinfunction "2_2") (pintype "passive"))
      (node (ref "L14") (pin "1") (pinfunction "1_1") (pintype "passive"))
      (node (ref "L15") (pin "2") (pinfunction "2_2") (pintype "passive"))
      (node (ref "U7") (pin "6") (pinfunction "VREG_6") (pintype "bidirectional"))
    )
    (net (code "87") (name "Net-(U7-XTA)") (class "Default")
      (node (ref "C38") (pin "1") (pinfunction "1_1") (pintype "passive"))
      (node (ref "U7") (pin "3") (pinfunction "XTA_3") (pintype "bidirectional"))
    )
    (net (code "88") (name "Net-(U8-IN)") (class "Default")
      (node (ref "C2") (pin "2") (pinfunction "2_2") (pintype "passive"))
      (node (ref "L11") (pin "2") (pinfunction "2_2") (pintype "passive"))
      (node (ref "R52") (pin "1") (pinfunction "1_1") (pintype "passive"))
      (node (ref "U8") (pin "2") (pinfunction "IN_2") (pintype "bidirectional"))
    )
    (net (code "89") (name "Net-(U8-OUT)") (class "Default")
      (node (ref "C8") (pin "1") (pinfunction "1_1") (pintype "passive"))
      (node (ref "R11") (pin "2") (pinfunction "2_2") (pintype "passive"))
      (node (ref "R52") (pin "2") (pinfunction "2_2") (pintype "passive"))
      (node (ref "U8") (pin "5") (pinfunction "OUT_5") (pintype "bidirectional"))
    )
    (net (code "90") (name "Net-(U9-ANT)") (class "Default")
      (node (ref "C59") (pin "2") (pinfunction "2_2") (pintype "passive"))
      (node (ref "C60") (pin "1") (pinfunction "1_1") (pintype "passive"))
      (node (ref "L17") (pin "1") (pinfunction "1_1") (pintype "passive"))
      (node (ref "U9") (pin "9") (pinfunction "ANT_9") (pintype "bidirectional"))
    )
    (net (code "91") (name "Net-(U9-CPS)") (class "Default")
      (node (ref "C17") (pin "2") (pinfunction "2_2") (pintype "passive"))
      (node (ref "R15") (pin "1") (pinfunction "1_1") (pintype "passive"))
      (node (ref "U9") (pin "5") (pinfunction "CPS_5") (pintype "bidirectional"))
    )
    (net (code "92") (name "Net-(U9-CSD)") (class "Default")
      (node (ref "C16") (pin "2") (pinfunction "2_2") (pintype "passive"))
      (node (ref "R14") (pin "1") (pinfunction "1_1") (pintype "passive"))
      (node (ref "U9") (pin "4") (pinfunction "CSD_4") (pintype "bidirectional"))
    )
    (net (code "93") (name "Net-(U9-CTX)") (class "Default")
      (node (ref "C18") (pin "2") (pinfunction "2_2") (pintype "passive"))
      (node (ref "R16") (pin "1") (pinfunction "1_1") (pintype "passive"))
      (node (ref "U9") (pin "6") (pinfunction "CTX_6") (pintype "bidirectional"))
    )
    (net (code "94") (name "Net-(U9-PA_OUT)") (class "Default")
      (node (ref "L2") (pin "1") (pinfunction "1_1") (pintype "passive"))
      (node (ref "L8") (pin "1") (pinfunction "1_1") (pintype "passive"))
      (node (ref "U9") (pin "13") (pinfunction "PA_OUT_13") (pintype "bidirectional"))
    )
    (net (code "95") (name "Net-(U9-RX)") (class "Default")
      (node (ref "C11") (pin "2") (pinfunction "2_2") (pintype "passive"))
      (node (ref "U9") (pin "2") (pinfunction "RX_2") (pintype "bidirectional"))
    )
    (net (code "96") (name "Net-(U9-RX_FLT)") (class "Default")
      (node (ref "R69") (pin "1") (pinfunction "1_1") (pintype "passive"))
      (node (ref "U9") (pin "8") (pinfunction "RX_FLT_8") (pintype "bidirectional"))
    )
    (net (code "97") (name "Net-(U9-TX)") (class "Default")
      (node (ref "C4") (pin "2") (pinfunction "2_2") (pintype "passive"))
      (node (ref "U9") (pin "1") (pinfunction "TX_1") (pintype "bidirectional"))
    )
    (net (code "98") (name "Net-(U9-TX_IN)") (class "Default")
      (node (ref "C58") (pin "2") (pinfunction "2_2") (pintype "passive"))
      (node (ref "L16") (pin "2") (pinfunction "2_2") (pintype "passive"))
      (node (ref "U9") (pin "11") (pinfunction "TX_IN_11") (pintype "bidirectional"))
    )
    (net (code "99") (name "Net-(U9-VCC0)") (class "Default")
      (node (ref "C52") (pin "2") (pinfunction "2_2") (pintype "passive"))
      (node (ref "FB1") (pin "1") (pinfunction "1_1") (pintype "bidirectional"))
      (node (ref "L1") (pin "2") (pinfunction "2_2") (pintype "passive"))
      (node (ref "U9") (pin "15") (pinfunction "VCC0_15") (pintype "bidirectional"))
    )
    (net (code "100") (name "Net-(U9-VCC1)") (class "Default")
      (node (ref "L1") (pin "1") (pinfunction "1_1") (pintype "passive"))
      (node (ref "U9") (pin "16") (pinfunction "VCC1_16") (pintype "bidirectional"))
    )
    (net (code "101") (name "Net-(U10-IN)") (class "Default")
      (node (ref "R35") (pin "2") (pinfunction "2_2") (pintype "passive"))
      (node (ref "R62") (pin "1") (pinfunction "1_1") (pintype "passive"))
      (node (ref "R69") (pin "2") (pinfunction "2_2") (pintype "passive"))
      (node (ref "U10") (pin "2") (pinfunction "IN_2") (pintype "bidirectional"))
    )
    (net (code "102") (name "Net-(U10-OUT)") (class "Default")
      (node (ref "R35") (pin "1") (pinfunction "1_1") (pintype "passive"))
      (node (ref "U10") (pin "5") (pinfunction "OUT_5") (pintype "bidirectional"))
      (node (ref "U9") (pin "7") (pinfunction "LNA_IN_7") (pintype "bidirectional"))
    )
    (net (code "103") (name "Net-(U11-DCC_SW)") (class "Default")
      (node (ref "L20") (pin "2") (pinfunction "2_2") (pintype "passive"))
      (node (ref "U11") (pin "9") (pinfunction "DCC_SW_9") (pintype "bidirectional"))
    )
    (net (code "104") (name "Net-(U11-MOSI)") (class "Default")
      (node (ref "R40") (pin "1") (pinfunction "1_1") (pintype "passive"))
      (node (ref "U11") (pin "17") (pinfunction "MOSI_17") (pintype "bidirectional"))
    )
    (net (code "105") (name "Net-(U11-SCK)") (class "Default")
      (node (ref "R41") (pin "1") (pinfunction "1_1") (pintype "passive"))
      (node (ref "U11") (pin "18") (pinfunction "SCK_18") (pintype "bidirectional"))
    )
    (net (code "106") (name "Net-(U11-VDD_IN)") (class "Default")
      (node (ref "C65") (pin "1") (pinfunction "1_1") (pintype "passive"))
      (node (ref "L18") (pin "2") (pinfunction "2_2") (pintype "passive"))
      (node (ref "R36") (pin "2") (pinfunction "2_2") (pintype "passive"))
      (node (ref "U11") (pin "1") (pinfunction "VDD_IN_1") (pintype "bidirectional"))
    )
    (net (code "107") (name "Net-(U11-VREG)") (class "Default")
      (node (ref "C63") (pin "1") (pinfunction "1_1") (pintype "passive"))
      (node (ref "L18") (pin "1") (pinfunction "1_1") (pintype "passive"))
      (node (ref "L20") (pin "1") (pinfunction "1_1") (pintype "passive"))
      (node (ref "U11") (pin "7") (pinfunction "VREG_7") (pintype "bidirectional"))
    )
    (net (code "108") (name "Net-(U11-XTA)") (class "Default")
      (node (ref "C66") (pin "1") (pinfunction "1_1") (pintype "passive"))
      (node (ref "U11") (pin "3") (pinfunction "XTA_3") (pintype "bidirectional"))
    )
    (net (code "109") (name "Net-(U12-BOOT0)") (class "Default")
      (node (ref "R56") (pin "2") (pinfunction "2_2") (pintype "passive"))
      (node (ref "R57") (pin "1") (pinfunction "1_1") (pintype "passive"))
      (node (ref "U12") (pin "31") (pinfunction "BOOT0_31") (pintype "bidirectional"))
    )
    (net (code "110") (name "Net-(U12-PA0-CLK_IN)") (class "Default")
      (node (ref "R72") (pin "2") (pinfunction "2_2") (pintype "passive"))
      (node (ref "R73") (pin "2") (pinfunction "2_2") (pintype "passive"))
      (node (ref "U12") (pin "6") (pinfunction "PA0-CLK_IN_6") (pintype "bidirectional"))
    )
    (net (code "111") (name "Net-(U12-PA11)") (class "Default")
      (node (ref "R66") (pin "2") (pinfunction "2_2") (pintype "passive"))
      (node (ref "U12") (pin "21") (pinfunction "PA11_21") (pintype "bidirectional"))
    )
    (net (code "112") (name "Net-(U12-PA12)") (class "Default")
      (node (ref "R64") (pin "2") (pinfunction "2_2") (pintype "passive"))
      (node (ref "U12") (pin "22") (pinfunction "PA12_22") (pintype "bidirectional"))
    )
    (net (code "113") (name "Net-(U12-PC14-OSC32_IN)") (class "Default")
      (node (ref "C81") (pin "1") (pinfunction "1_1") (pintype "passive"))
      (node (ref "U12") (pin "2") (pinfunction "PC14-OSC32_IN_2") (pintype "bidirectional"))
      (node (ref "X3") (pin "2") (pinfunction "2_2") (pintype "passive"))
    )
    (net (code "114") (name "Net-(U12-PC15-OSC32_OUT)") (class "Default")
      (node (ref "C84") (pin "1") (pinfunction "1_1") (pintype "passive"))
      (node (ref "U12") (pin "3") (pinfunction "PC15-OSC32_OUT_3") (pintype "bidirectional"))
      (node (ref "X3") (pin "1") (pinfunction "1_1") (pintype "passive"))
    )
    (net (code "115") (name "Net-(U13-~{EVENT})") (class "Default")
      (node (ref "R65") (pin "2") (pinfunction "2_2") (pintype "passive"))
      (node (ref "U13") (pin "2") (pinfunction "~{EVENT}_2") (pintype "bidirectional"))
    )
    (net (code "116") (name "Net-(X1-ENABLE)") (class "Default")
      (node (ref "R3") (pin "1") (pinfunction "1_1") (pintype "passive"))
      (node (ref "R4") (pin "2") (pinfunction "2_2") (pintype "passive"))
      (node (ref "X1") (pin "1") (pinfunction "ENABLE_1") (pintype "bidirectional"))
    )
    (net (code "117") (name "Net-(X1-VDD)") (class "Default")
      (node (ref "C62") (pin "2") (pinfunction "2_2") (pintype "passive"))
      (node (ref "L4") (pin "1") (pinfunction "1_1") (pintype "bidirectional"))
      (node (ref "R3") (pin "2") (pinfunction "2_2") (pintype "passive"))
      (node (ref "X1") (pin "4") (pinfunction "VDD_4") (pintype "bidirectional"))
    )
    (net (code "118") (name "PPS") (class "Default")
      (node (ref "J1") (pin "19") (pinfunction "19_19") (pintype "bidirectional"))
      (node (ref "TP2") (pin "T") (pinfunction "T_T") (pintype "bidirectional"))
      (node (ref "U1") (pin "8") (pinfunction "PPS_8") (pintype "bidirectional"))
      (node (ref "U12") (pin "27") (pinfunction "PB4_27") (pintype "bidirectional"))
    )
    (net (code "119") (name "RADIO_A_CLK_32M") (class "Default")
      (node (ref "R25") (pin "2") (pinfunction "2_2") (pintype "passive"))
      (node (ref "R72") (pin "1") (pinfunction "1_1") (pintype "passive"))
      (node (ref "U5") (pin "14") (pinfunction "BUSY_14") (pintype "bidirectional"))
    )
    (net (code "120") (name "RADIO_A_CLK_O") (class "Default")
      (node (ref "R28") (pin "2") (pinfunction "2_2") (pintype "passive"))
      (node (ref "U5") (pin "11") (pinfunction "DIO5_11") (pintype "bidirectional"))
    )
    (net (code "121") (name "RADIO_A_CSN") (class "Default")
      (node (ref "U1") (pin "68") (pinfunction "RADIO_A_CSN_68") (pintype "bidirectional"))
      (node (ref "U5") (pin "19") (pinfunction "NSS_19") (pintype "bidirectional"))
    )
    (net (code "122") (name "RADIO_A_IQ_0") (class "Default")
      (node (ref "R26") (pin "2") (pinfunction "2_2") (pintype "passive"))
      (node (ref "U5") (pin "13") (pinfunction "DIO1_13") (pintype "bidirectional"))
    )
    (net (code "123") (name "RADIO_A_IQ_1") (class "Default")
      (node (ref "R27") (pin "2") (pinfunction "2_2") (pintype "passive"))
      (node (ref "U5") (pin "12") (pinfunction "DIO2_12") (pintype "bidirectional"))
    )
    (net (code "124") (name "RADIO_A_IQ_2") (class "Default")
      (node (ref "R29") (pin "2") (pinfunction "2_2") (pintype "passive"))
      (node (ref "U5") (pin "5") (pinfunction "DIO3_5") (pintype "bidirectional"))
    )
    (net (code "125") (name "RADIO_A_IQ_3") (class "Default")
      (node (ref "R24") (pin "2") (pinfunction "2_2") (pintype "passive"))
      (node (ref "U5") (pin "21") (pinfunction "DIO4_21") (pintype "bidirectional"))
    )
    (net (code "126") (name "RADIO_A_RESET") (class "Default")
      (node (ref "U1") (pin "13") (pinfunction "RADIO_CTRL3_13") (pintype "bidirectional"))
      (node (ref "U5") (pin "15") (pinfunction "NRESET_15") (pintype "bidirectional"))
    )
    (net (code "127") (name "RADIO_A_RFIN") (class "Default")
      (node (ref "C6") (pin "2") (pinfunction "2_2") (pintype "passive"))
      (node (ref "L12") (pin "2") (pinfunction "2_2") (pintype "passive"))
      (node (ref "U5") (pin "23") (pinfunction "RFI_N_23") (pintype "bidirectional"))
    )
    (net (code "128") (name "RADIO_A_RFIP") (class "Default")
      (node (ref "C5") (pin "2") (pinfunction "2_2") (pintype "passive"))
      (node (ref "L12") (pin "1") (pinfunction "1_1") (pintype "passive"))
      (node (ref "U5") (pin "22") (pinfunction "RFI_P_22") (pintype "bidirectional"))
    )
    (net (code "129") (name "RADIO_B_CLK_32M") (class "Default")
      (node (ref "R19") (pin "2") (pinfunction "2_2") (pintype "passive"))
      (node (ref "U7") (pin "14") (pinfunction "BUSY_14") (pintype "bidirectional"))
    )
    (net (code "130") (name "RADIO_B_CLK_O") (class "Default")
      (node (ref "R22") (pin "2") (pinfunction "2_2") (pintype "passive"))
      (node (ref "U7") (pin "11") (pinfunction "DIO5_11") (pintype "bidirectional"))
    )
    (net (code "131") (name "RADIO_B_CSN") (class "Default")
      (node (ref "U1") (pin "18") (pinfunction "RADIO_B_CSN_18") (pintype "bidirectional"))
      (node (ref "U7") (pin "19") (pinfunction "NSS_19") (pintype "bidirectional"))
    )
    (net (code "132") (name "RADIO_B_IQ0") (class "Default")
      (node (ref "R20") (pin "2") (pinfunction "2_2") (pintype "passive"))
      (node (ref "U7") (pin "13") (pinfunction "DIO1_13") (pintype "bidirectional"))
    )
    (net (code "133") (name "RADIO_B_IQ_1") (class "Default")
      (node (ref "R21") (pin "2") (pinfunction "2_2") (pintype "passive"))
      (node (ref "U7") (pin "12") (pinfunction "DIO2_12") (pintype "bidirectional"))
    )
    (net (code "134") (name "RADIO_B_IQ_2") (class "Default")
      (node (ref "R23") (pin "2") (pinfunction "2_2") (pintype "passive"))
      (node (ref "U7") (pin "5") (pinfunction "DIO3_5") (pintype "bidirectional"))
    )
    (net (code "135") (name "RADIO_B_IQ_3") (class "Default")
      (node (ref "R18") (pin "2") (pinfunction "2_2") (pintype "passive"))
      (node (ref "U7") (pin "21") (pinfunction "DIO4_21") (pintype "bidirectional"))
    )
    (net (code "136") (name "RADIO_B_RESET") (class "Default")
      (node (ref "U1") (pin "28") (pinfunction "RADIO_CTRL9_28") (pintype "bidirectional"))
      (node (ref "U7") (pin "15") (pinfunction "NRESET_15") (pintype "bidirectional"))
    )
    (net (code "137") (name "RADIO_B_RFIN") (class "Default")
      (node (ref "C10") (pin "2") (pinfunction "2_2") (pintype "passive"))
      (node (ref "L13") (pin "2") (pinfunction "2_2") (pintype "passive"))
      (node (ref "U7") (pin "23") (pinfunction "RFI_N_23") (pintype "bidirectional"))
    )
    (net (code "138") (name "RADIO_B_RFIP") (class "Default")
      (node (ref "C9") (pin "2") (pinfunction "2_2") (pintype "passive"))
      (node (ref "L13") (pin "1") (pinfunction "1_1") (pintype "passive"))
      (node (ref "U7") (pin "22") (pinfunction "RFI_P_22") (pintype "bidirectional"))
    )
    (net (code "139") (name "RFO") (class "Default")
      (node (ref "C53") (pin "1") (pinfunction "1_1") (pintype "passive"))
      (node (ref "L10") (pin "1") (pinfunction "1_1") (pintype "passive"))
      (node (ref "L9") (pin "1") (pinfunction "1_1") (pintype "passive"))
      (node (ref "U5") (pin "24") (pinfunction "RFO_24") (pintype "bidirectional"))
    )
    (net (code "140") (name "RX_ON") (class "Default")
      (node (ref "R32") (pin "1") (pinfunction "1_1") (pintype "passive"))
      (node (ref "U1") (pin "59") (pinfunction "GPIO4_59") (pintype "bidirectional"))
    )
    (net (code "141") (name "SCK") (class "Default")
      (node (ref "R10") (pin "2") (pinfunction "2_2") (pintype "passive"))
      (node (ref "R41") (pin "2") (pinfunction "2_2") (pintype "passive"))
      (node (ref "R49") (pin "1") (pinfunction "1_1") (pintype "passive"))
      (node (ref "R50") (pin "1") (pinfunction "1_1") (pintype "passive"))
    )
    (net (code "142") (name "SCK_A") (class "Default")
      (node (ref "U1") (pin "65") (pinfunction "RADIO_A_SCK_65") (pintype "bidirectional"))
      (node (ref "U5") (pin "18") (pinfunction "SCK_18") (pintype "bidirectional"))
    )
    (net (code "143") (name "SCK_B") (class "Default")
      (node (ref "U1") (pin "21") (pinfunction "RADIO_B_SCK_21") (pintype "bidirectional"))
      (node (ref "U7") (pin "18") (pinfunction "SCK_18") (pintype "bidirectional"))
    )
    (net (code "144") (name "STM32_MISO") (class "Default")
      (node (ref "R45") (pin "2") (pinfunction "2_2") (pintype "passive"))
      (node (ref "U12") (pin "12") (pinfunction "PA6_12") (pintype "bidirectional"))
    )
    (net (code "145") (name "STM32_MOSI") (class "Default")
      (node (ref "R48") (pin "2") (pinfunction "2_2") (pintype "passive"))
      (node (ref "U12") (pin "13") (pinfunction "PA7_13") (pintype "bidirectional"))
    )
    (net (code "146") (name "STM32_SCK") (class "Default")
      (node (ref "R50") (pin "2") (pinfunction "2_2") (pintype "passive"))
      (node (ref "U12") (pin "11") (pinfunction "PA5_11") (pintype "bidirectional"))
    )
    (net (code "147") (name "SWCLK") (class "Default")
      (node (ref "TP7") (pin "T") (pinfunction "T_T") (pintype "bidirectional"))
      (node (ref "U12") (pin "24") (pinfunction "PA14_24") (pintype "bidirectional"))
    )
    (net (code "148") (name "SWDIO") (class "Default")
      (node (ref "TP8") (pin "T") (pinfunction "T_T") (pintype "bidirectional"))
      (node (ref "U12") (pin "23") (pinfunction "PA13_23") (pintype "bidirectional"))
    )
    (net (code "149") (name "SX1261_BUSY") (class "Default")
      (node (ref "R67") (pin "1") (pinfunction "1_1") (pintype "passive"))
      (node (ref "U11") (pin "14") (pinfunction "BUSY_14") (pintype "bidirectional"))
      (node (ref "U12") (pin "9") (pinfunction "PA3_9") (pintype "bidirectional"))
    )
    (net (code "150") (name "SX1261_CS") (class "Default")
      (node (ref "R42") (pin "1") (pinfunction "1_1") (pintype "passive"))
      (node (ref "R51") (pin "1") (pinfunction "1_1") (pintype "passive"))
      (node (ref "U11") (pin "19") (pinfunction "NSS_19") (pintype "bidirectional"))
      (node (ref "U12") (pin "14") (pinfunction "PB0_14") (pintype "bidirectional"))
    )
    (net (code "151") (name "SX1261_IO1") (class "Default")
      (node (ref "R61") (pin "1") (pinfunction "1_1") (pintype "passive"))
      (node (ref "U1") (pin "54") (pinfunction "GPIO7_54") (pintype "bidirectional"))
      (node (ref "U11") (pin "13") (pinfunction "DIO1_13") (pintype "bidirectional"))
      (node (ref "U12") (pin "15") (pinfunction "PB1_15") (pintype "bidirectional"))
    )
    (net (code "152") (name "SX1261_IO2") (class "Default")
      (node (ref "R63") (pin "1") (pinfunction "1_1") (pintype "passive"))
      (node (ref "U11") (pin "12") (pinfunction "DIO2_12") (pintype "bidirectional"))
    )
    (net (code "153") (name "SX1261_IO3") (class "Default")
      (node (ref "TP9") (pin "T") (pinfunction "T_T") (pintype "bidirectional"))
      (node (ref "U11") (pin "6") (pinfunction "DIO3_6") (pintype "bidirectional"))
    )
    (net (code "154") (name "SX1261_RFIN") (class "Default")
      (node (ref "C68") (pin "2") (pinfunction "2_2") (pintype "passive"))
      (node (ref "L22") (pin "2") (pinfunction "2_2") (pintype "passive"))
      (node (ref "U11") (pin "22") (pinfunction "RFI_N_22") (pintype "bidirectional"))
    )
    (net (code "155") (name "SX1261_RFIP") (class "Default")
      (node (ref "C73") (pin "1") (pinfunction "1_1") (pintype "passive"))
      (node (ref "L22") (pin "1") (pinfunction "1_1") (pintype "passive"))
      (node (ref "U11") (pin "21") (pinfunction "RFI_P_21") (pintype "bidirectional"))
    )
    (net (code "156") (name "SX1261_RST") (class "Default")
      (node (ref "R38") (pin "1") (pinfunction "1_1") (pintype "passive"))
      (node (ref "R60") (pin "1") (pinfunction "1_1") (pintype "passive"))
      (node (ref "U11") (pin "15") (pinfunction "NRESET_15") (pintype "bidirectional"))
      (node (ref "U12") (pin "18") (pinfunction "PA8_18") (pintype "bidirectional"))
    )
    (net (code "157") (name "SX1302_GPIO8") (class "Default")
      (node (ref "U1") (pin "53") (pinfunction "GPIO8_53") (pintype "bidirectional"))
      (node (ref "U12") (pin "26") (pinfunction "PB3_26") (pintype "bidirectional"))
    )
    (net (code "158") (name "TX_ON") (class "Default")
      (node (ref "R30") (pin "1") (pinfunction "1_1") (pintype "passive"))
      (node (ref "U1") (pin "63") (pinfunction "GPIO2_63") (pintype "bidirectional"))
    )
    (net (code "159") (name "TX_RX_SW") (class "Default")
      (node (ref "R16") (pin "2") (pinfunction "2_2") (pintype "passive"))
      (node (ref "U1") (pin "12") (pinfunction "RADIO_CTRL2_12") (pintype "bidirectional"))
    )
    (net (code "160") (name "VCCIO") (class "Default")
      (node (ref "C19") (pin "2") (pinfunction "2_2") (pintype "passive"))
      (node (ref "C20") (pin "2") (pinfunction "2_2") (pintype "passive"))
      (node (ref "C25") (pin "2") (pinfunction "2_2") (pintype "passive"))
      (node (ref "C28") (pin "2") (pinfunction "2_2") (pintype "passive"))
      (node (ref "C3") (pin "2") (pinfunction "2_2") (pintype "passive"))
      (node (ref "C41") (pin "2") (pinfunction "2_2") (pintype "passive"))
      (node (ref "C42") (pin "2") (pinfunction "2_2") (pintype "passive"))
      (node (ref "C45") (pin "2") (pinfunction "2_2") (pintype "passive"))
      (node (ref "C47") (pin "2") (pinfunction "2_2") (pintype "passive"))
      (node (ref "C76") (pin "2") (pinfunction "2_2") (pintype "passive"))
      (node (ref "C80") (pin "2") (pinfunction "2_2") (pintype "passive"))
      (node (ref "C83") (pin "2") (pinfunction "2_2") (pintype "passive"))
      (node (ref "C86") (pin "2") (pinfunction "2_2") (pintype "passive"))
      (node (ref "C87") (pin "2") (pinfunction "2_2") (pintype "passive"))
      (node (ref "C88") (pin "2") (pinfunction "2_2") (pintype "passive"))
      (node (ref "C89") (pin "2") (pinfunction "2_2") (pintype "passive"))
      (node (ref "C90") (pin "2") (pinfunction "2_2") (pintype "passive"))
      (node (ref "Q8") (pin "3") (pinfunction "D_3") (pintype "passive"))
      (node (ref "R33") (pin "1") (pinfunction "1_1") (pintype "passive"))
      (node (ref "R34") (pin "2") (pinfunction "2_2") (pintype "passive"))
      (node (ref "R56") (pin "1") (pinfunction "1_1") (pintype "passive"))
      (node (ref "R58") (pin "1") (pinfunction "1_1") (pintype "passive"))
      (node (ref "R65") (pin "1") (pinfunction "1_1") (pintype "passive"))
      (node (ref "R68") (pin "1") (pinfunction "1_1") (pintype "passive"))
      (node (ref "R71") (pin "1") (pinfunction "1_1") (pintype "passive"))
      (node (ref "R80") (pin "2") (pinfunction "2_2") (pintype "passive"))
      (node (ref "TP1") (pin "T") (pinfunction "T_T") (pintype "bidirectional"))
      (node (ref "U1") (pin "14") (pinfunction "VCC_IO_14") (pintype "bidirectional"))
      (node (ref "U1") (pin "30") (pinfunction "VCC_IO_30") (pintype "bidirectional"))
      (node (ref "U1") (pin "47") (pinfunction "VCC_IO_47") (pintype "bidirectional"))
      (node (ref "U1") (pin "61") (pinfunction "VCC_IO_61") (pintype "bidirectional"))
      (node (ref "U12") (pin "1") (pinfunction "VDD_1") (pintype "bidirectional"))
      (node (ref "U12") (pin "17") (pinfunction "VDD_17") (pintype "bidirectional"))
      (node (ref "U12") (pin "5") (pinfunction "VDDA_5") (pintype "bidirectional"))
      (node (ref "U13") (pin "3") (pinfunction "VDD_3") (pintype "bidirectional"))
    )
    (net (code "161") (name "VCC_1V2") (class "Default")
      (node (ref "C12") (pin "2") (pinfunction "2_2") (pintype "passive"))
      (node (ref "C13") (pin "2") (pinfunction "2_2") (pintype "passive"))
      (node (ref "C23") (pin "2") (pinfunction "2_2") (pintype "passive"))
      (node (ref "C24") (pin "2") (pinfunction "2_2") (pintype "passive"))
      (node (ref "C29") (pin "2") (pinfunction "2_2") (pintype "passive"))
      (node (ref "C40") (pin "2") (pinfunction "2_2") (pintype "passive"))
      (node (ref "C43") (pin "2") (pinfunction "2_2") (pintype "passive"))
      (node (ref "C44") (pin "2") (pinfunction "2_2") (pintype "passive"))
      (node (ref "C71") (pin "2") (pinfunction "2_2") (pintype "passive"))
      (node (ref "C72") (pin "2") (pinfunction "2_2") (pintype "passive"))
      (node (ref "L5") (pin "2") (pinfunction "2_2") (pintype "passive"))
      (node (ref "R79") (pin "1") (pinfunction "1_1") (pintype "passive"))
      (node (ref "R83") (pin "2") (pinfunction "2_2") (pintype "passive"))
      (node (ref "TP14") (pin "T") (pinfunction "T_T") (pintype "bidirectional"))
      (node (ref "U1") (pin "23") (pinfunction "VCC_CORE_23") (pintype "bidirectional"))
      (node (ref "U1") (pin "40") (pinfunction "VCC_CORE_40") (pintype "bidirectional"))
      (node (ref "U1") (pin "5") (pinfunction "VCC_CORE_5") (pintype "bidirectional"))
      (node (ref "U1") (pin "56") (pinfunction "VCC_CORE_56") (pintype "bidirectional"))
      (node (ref "U6") (pin "5") (pinfunction "OUT_5") (pintype "bidirectional"))
    )
    (net (code "162") (name "VCC_FEM") (class "Default")
      (node (ref "C26") (pin "2") (pinfunction "2_2") (pintype "passive"))
      (node (ref "C27") (pin "2") (pinfunction "2_2") (pintype "passive"))
      (node (ref "C49") (pin "2") (pinfunction "2_2") (pintype "passive"))
      (node (ref "C50") (pin "2") (pinfunction "2_2") (pintype "passive"))
      (node (ref "C51") (pin "2") (pinfunction "2_2") (pintype "passive"))
      (node (ref "C55") (pin "2") (pinfunction "2_2") (pintype "passive"))
      (node (ref "FB1") (pin "2") (pinfunction "2_2") (pintype "bidirectional"))
      (node (ref "L2") (pin "2") (pinfunction "2_2") (pintype "passive"))
      (node (ref "R2") (pin "2") (pinfunction "2_2") (pintype "passive"))
      (node (ref "TP6") (pin "T") (pinfunction "T_T") (pintype "bidirectional"))
      (node (ref "U3") (pin "5") (pinfunction "VOUT_5") (pintype "bidirectional"))
    )
    (net (code "163") (name "VCC_RADIO") (class "Default")
      (node (ref "C21") (pin "2") (pinfunction "2_2") (pintype "passive"))
      (node (ref "C32") (pin "2") (pinfunction "2_2") (pintype "passive"))
      (node (ref "C33") (pin "2") (pinfunction "2_2") (pintype "passive"))
      (node (ref "C35") (pin "2") (pinfunction "2_2") (pintype "passive"))
      (node (ref "C39") (pin "2") (pinfunction "2_2") (pintype "passive"))
      (node (ref "C48") (pin "2") (pinfunction "2_2") (pintype "passive"))
      (node (ref "C67") (pin "1") (pinfunction "1_1") (pintype "passive"))
      (node (ref "L15") (pin "1") (pinfunction "1_1") (pintype "passive"))
      (node (ref "L4") (pin "2") (pinfunction "2_2") (pintype "bidirectional"))
      (node (ref "L7") (pin "1") (pinfunction "1_1") (pintype "passive"))
      (node (ref "R36") (pin "1") (pinfunction "1_1") (pintype "passive"))
      (node (ref "R38") (pin "2") (pinfunction "2_2") (pintype "passive"))
      (node (ref "R42") (pin "2") (pinfunction "2_2") (pintype "passive"))
      (node (ref "R7") (pin "2") (pinfunction "2_2") (pintype "passive"))
      (node (ref "TP10") (pin "T") (pinfunction "T_T") (pintype "bidirectional"))
      (node (ref "U11") (pin "10") (pinfunction "VBAT_10") (pintype "bidirectional"))
      (node (ref "U11") (pin "11") (pinfunction "VBAT_IO_11") (pintype "bidirectional"))
      (node (ref "U4") (pin "5") (pinfunction "VOUT_5") (pintype "bidirectional"))
      (node (ref "U5") (pin "10") (pinfunction "VBAT_DIO_10") (pintype "bidirectional"))
      (node (ref "U5") (pin "2") (pinfunction "VDD_IN_2") (pintype "bidirectional"))
      (node (ref "U5") (pin "9") (pinfunction "VBAT_RF_9") (pintype "bidirectional"))
      (node (ref "U7") (pin "10") (pinfunction "VBAT_DIO_10") (pintype "bidirectional"))
      (node (ref "U7") (pin "2") (pinfunction "VDD_IN_2") (pintype "bidirectional"))
      (node (ref "U7") (pin "9") (pinfunction "VBAT_RF_9") (pintype "bidirectional"))
    )
    (net (code "164") (name "VIN") (class "Default")
      (node (ref "C15") (pin "2") (pinfunction "2_2") (pintype "passive"))
      (node (ref "C22") (pin "2") (pinfunction "2_2") (pintype "passive"))
      (node (ref "C30") (pin "2") (pinfunction "2_2") (pintype "passive"))
      (node (ref "C31") (pin "2") (pinfunction "2_2") (pintype "passive"))
      (node (ref "C69") (pin "2") (pinfunction "2_2") (pintype "passive"))
      (node (ref "C70") (pin "2") (pinfunction "2_2") (pintype "passive"))
      (node (ref "J1") (pin "2") (pinfunction "3V3_2") (pintype "bidirectional"))
      (node (ref "J1") (pin "24") (pinfunction "3V3_24") (pintype "bidirectional"))
      (node (ref "J1") (pin "39") (pinfunction "3V3_39") (pintype "bidirectional"))
      (node (ref "J1") (pin "41") (pinfunction "3V3_41") (pintype "bidirectional"))
      (node (ref "J1") (pin "52") (pinfunction "3V3_52") (pintype "bidirectional"))
      (node (ref "Q8") (pin "2") (pinfunction "S_2") (pintype "passive"))
      (node (ref "R2") (pin "1") (pinfunction "1_1") (pintype "passive"))
      (node (ref "R47") (pin "1") (pinfunction "1_1") (pintype "passive"))
      (node (ref "R7") (pin "1") (pinfunction "1_1") (pintype "passive"))
      (node (ref "R78") (pin "1") (pinfunction "1_1") (pintype "passive"))
      (node (ref "R8") (pin "2") (pinfunction "2_2") (pintype "passive"))
      (node (ref "R82") (pin "1") (pinfunction "1_1") (pintype "passive"))
      (node (ref "TP4") (pin "T") (pinfunction "T_T") (pintype "bidirectional"))
      (node (ref "U3") (pin "1") (pinfunction "VIN_1") (pintype "bidirectional"))
      (node (ref "U4") (pin "1") (pinfunction "VIN_1") (pintype "bidirectional"))
      (node (ref "U6") (pin "2") (pinfunction "VIN_2") (pintype "bidirectional"))
    )
    (net (code "165") (name "unconnected-(J1-1V5-Pad6)") (class "Default")
      (node (ref "J1") (pin "6") (pinfunction "1V5_6") (pintype "bidirectional"))
    )
    (net (code "166") (name "unconnected-(J1-1V5-Pad28)") (class "Default")
      (node (ref "J1") (pin "28") (pinfunction "1V5_28") (pintype "bidirectional"))
    )
    (net (code "167") (name "unconnected-(J1-1V5-Pad48)") (class "Default")
      (node (ref "J1") (pin "48") (pinfunction "1V5_48") (pintype "bidirectional"))
    )
    (net (code "168") (name "unconnected-(J1-Pad1)") (class "Default")
      (node (ref "J1") (pin "1") (pinfunction "1_1") (pintype "bidirectional"))
    )
    (net (code "169") (name "unconnected-(J1-Pad3)") (class "Default")
      (node (ref "J1") (pin "3") (pinfunction "3_3") (pintype "bidirectional"))
    )
    (net (code "170") (name "unconnected-(J1-Pad5)") (class "Default")
      (node (ref "J1") (pin "5") (pinfunction "5_5") (pintype "bidirectional"))
    )
    (net (code "171") (name "unconnected-(J1-Pad7)") (class "Default")
      (node (ref "J1") (pin "7") (pinfunction "7_7") (pintype "bidirectional"))
    )
    (net (code "172") (name "unconnected-(J1-Pad11)") (class "Default")
      (node (ref "J1") (pin "11") (pinfunction "11_11") (pintype "bidirectional"))
    )
    (net (code "173") (name "unconnected-(J1-Pad13)") (class "Default")
      (node (ref "J1") (pin "13") (pinfunction "13_13") (pintype "bidirectional"))
    )
    (net (code "174") (name "unconnected-(J1-Pad17)") (class "Default")
      (node (ref "J1") (pin "17") (pinfunction "17_17") (pintype "bidirectional"))
    )
    (net (code "175") (name "unconnected-(J1-Pad20)") (class "Default")
      (node (ref "J1") (pin "20") (pinfunction "20_20") (pintype "bidirectional"))
    )
    (net (code "176") (name "unconnected-(J1-Pad42)") (class "Default")
      (node (ref "J1") (pin "42") (pinfunction "42_42") (pintype "bidirectional"))
    )
    (net (code "177") (name "unconnected-(J1-Pad44)") (class "Default")
      (node (ref "J1") (pin "44") (pinfunction "44_44") (pintype "bidirectional"))
    )
    (net (code "178") (name "unconnected-(J1-Pad46)") (class "Default")
      (node (ref "J1") (pin "46") (pinfunction "46_46") (pintype "bidirectional"))
    )
    (net (code "179") (name "unconnected-(U1-GPIO1-Pad64)") (class "Default")
      (node (ref "U1") (pin "64") (pinfunction "GPIO1_64") (pintype "bidirectional"))
    )
    (net (code "180") (name "unconnected-(U1-GPIO3-Pad60)") (class "Default")
      (node (ref "U1") (pin "60") (pinfunction "GPIO3_60") (pintype "bidirectional"))
    )
    (net (code "181") (name "unconnected-(U1-GPIO5-Pad58)") (class "Default")
      (node (ref "U1") (pin "58") (pinfunction "GPIO5_58") (pintype "bidirectional"))
    )
    (net (code "182") (name "unconnected-(U1-GPIO6-Pad57)") (class "Default")
      (node (ref "U1") (pin "57") (pinfunction "GPIO6_57") (pintype "bidirectional"))
    )
    (net (code "183") (name "unconnected-(U1-GPIO9-Pad52)") (class "Default")
      (node (ref "U1") (pin "52") (pinfunction "GPIO9_52") (pintype "bidirectional"))
    )
    (net (code "184") (name "unconnected-(U1-GPIO10-Pad51)") (class "Default")
      (node (ref "U1") (pin "51") (pinfunction "GPIO10_51") (pintype "bidirectional"))
    )
    (net (code "185") (name "unconnected-(U1-GPIO11-Pad50)") (class "Default")
      (node (ref "U1") (pin "50") (pinfunction "GPIO11_50") (pintype "bidirectional"))
    )
    (net (code "186") (name "unconnected-(U1-RADIO_CTRL1-Pad11)") (class "Default")
      (node (ref "U1") (pin "11") (pinfunction "RADIO_CTRL1_11") (pintype "bidirectional"))
    )
    (net (code "187") (name "unconnected-(U1-RADIO_CTRL5-Pad17)") (class "Default")
      (node (ref "U1") (pin "17") (pinfunction "RADIO_CTRL5_17") (pintype "bidirectional"))
    )
    (net (code "188") (name "unconnected-(U1-RADIO_CTRL6-Pad22)") (class "Default")
      (node (ref "U1") (pin "22") (pinfunction "RADIO_CTRL6_22") (pintype "bidirectional"))
    )
    (net (code "189") (name "unconnected-(U1-RADIO_CTRL7-Pad26)") (class "Default")
      (node (ref "U1") (pin "26") (pinfunction "RADIO_CTRL7_26") (pintype "bidirectional"))
    )
    (net (code "190") (name "unconnected-(U1-RADIO_CTRL8-Pad27)") (class "Default")
      (node (ref "U1") (pin "27") (pinfunction "RADIO_CTRL8_27") (pintype "bidirectional"))
    )
    (net (code "191") (name "unconnected-(U1-RADIO_CTRL10-Pad29)") (class "Default")
      (node (ref "U1") (pin "29") (pinfunction "RADIO_CTRL10_29") (pintype "bidirectional"))
    )
    (net (code "192") (name "unconnected-(U1-RADIO_CTRL11-Pad31)") (class "Default")
      (node (ref "U1") (pin "31") (pinfunction "RADIO_CTRL11_31") (pintype "bidirectional"))
    )
    (net (code "193") (name "unconnected-(U3-NC-Pad4)") (class "Default")
      (node (ref "U3") (pin "4") (pinfunction "NC_4") (pintype "bidirectional"))
    )
    (net (code "194") (name "unconnected-(U4-NC-Pad4)") (class "Default")
      (node (ref "U4") (pin "4") (pinfunction "NC_4") (pintype "bidirectional"))
    )
    (net (code "195") (name "unconnected-(U5-XTB-Pad4)") (class "Default")
      (node (ref "U5") (pin "4") (pinfunction "XTB_4") (pintype "bidirectional"))
    )
    (net (code "196") (name "unconnected-(U7-RFO-Pad24)") (class "Default")
      (node (ref "U7") (pin "24") (pinfunction "RFO_24") (pintype "bidirectional"))
    )
    (net (code "197") (name "unconnected-(U7-VR_PA-Pad1)") (class "Default")
      (node (ref "U7") (pin "1") (pinfunction "VR_PA_1") (pintype "bidirectional"))
    )
    (net (code "198") (name "unconnected-(U7-XTB-Pad4)") (class "Default")
      (node (ref "U7") (pin "4") (pinfunction "XTB_4") (pintype "bidirectional"))
    )
    (net (code "199") (name "unconnected-(U9-NC-Pad14)") (class "Default")
      (node (ref "U9") (pin "14") (pinfunction "NC_14") (pintype "bidirectional"))
    )
    (net (code "200") (name "unconnected-(U9-TX_ALT-Pad3)") (class "Default")
      (node (ref "U9") (pin "3") (pinfunction "TX_ALT_3") (pintype "bidirectional"))
    )
    (net (code "201") (name "unconnected-(U11-RFO-Pad23)") (class "Default")
      (node (ref "U11") (pin "23") (pinfunction "RFO_23") (pintype "bidirectional"))
    )
    (net (code "202") (name "unconnected-(U11-VR_PA-Pad24)") (class "Default")
      (node (ref "U11") (pin "24") (pinfunction "VR_PA_24") (pintype "bidirectional"))
    )
    (net (code "203") (name "unconnected-(U11-XTB-Pad4)") (class "Default")
      (node (ref "U11") (pin "4") (pinfunction "XTB_4") (pintype "bidirectional"))
    )
    (net (code "204") (name "unconnected-(U12-PA1-Pad7)") (class "Default")
      (node (ref "U12") (pin "7") (pinfunction "PA1_7") (pintype "bidirectional"))
    )
    (net (code "205") (name "unconnected-(U12-PA9-Pad19)") (class "Default")
      (node (ref "U12") (pin "19") (pinfunction "PA9_19") (pintype "bidirectional"))
    )
    (net (code "206") (name "unconnected-(U12-PA10-Pad20)") (class "Default")
      (node (ref "U12") (pin "20") (pinfunction "PA10_20") (pintype "bidirectional"))
    )
    (net (code "207") (name "unconnected-(U12-PA15-Pad25)") (class "Default")
      (node (ref "U12") (pin "25") (pinfunction "PA15_25") (pintype "bidirectional"))
    )
    (net (code "208") (name "unconnected-(U12-PB5-Pad28)") (class "Default")
      (node (ref "U12") (pin "28") (pinfunction "PB5_28") (pintype "bidirectional"))
    )
  )
)
